# ProPrj_Custom_Keyboard_2025-10-10.net
KiCad netlist of a schematic drawn in EasyEDA Pro
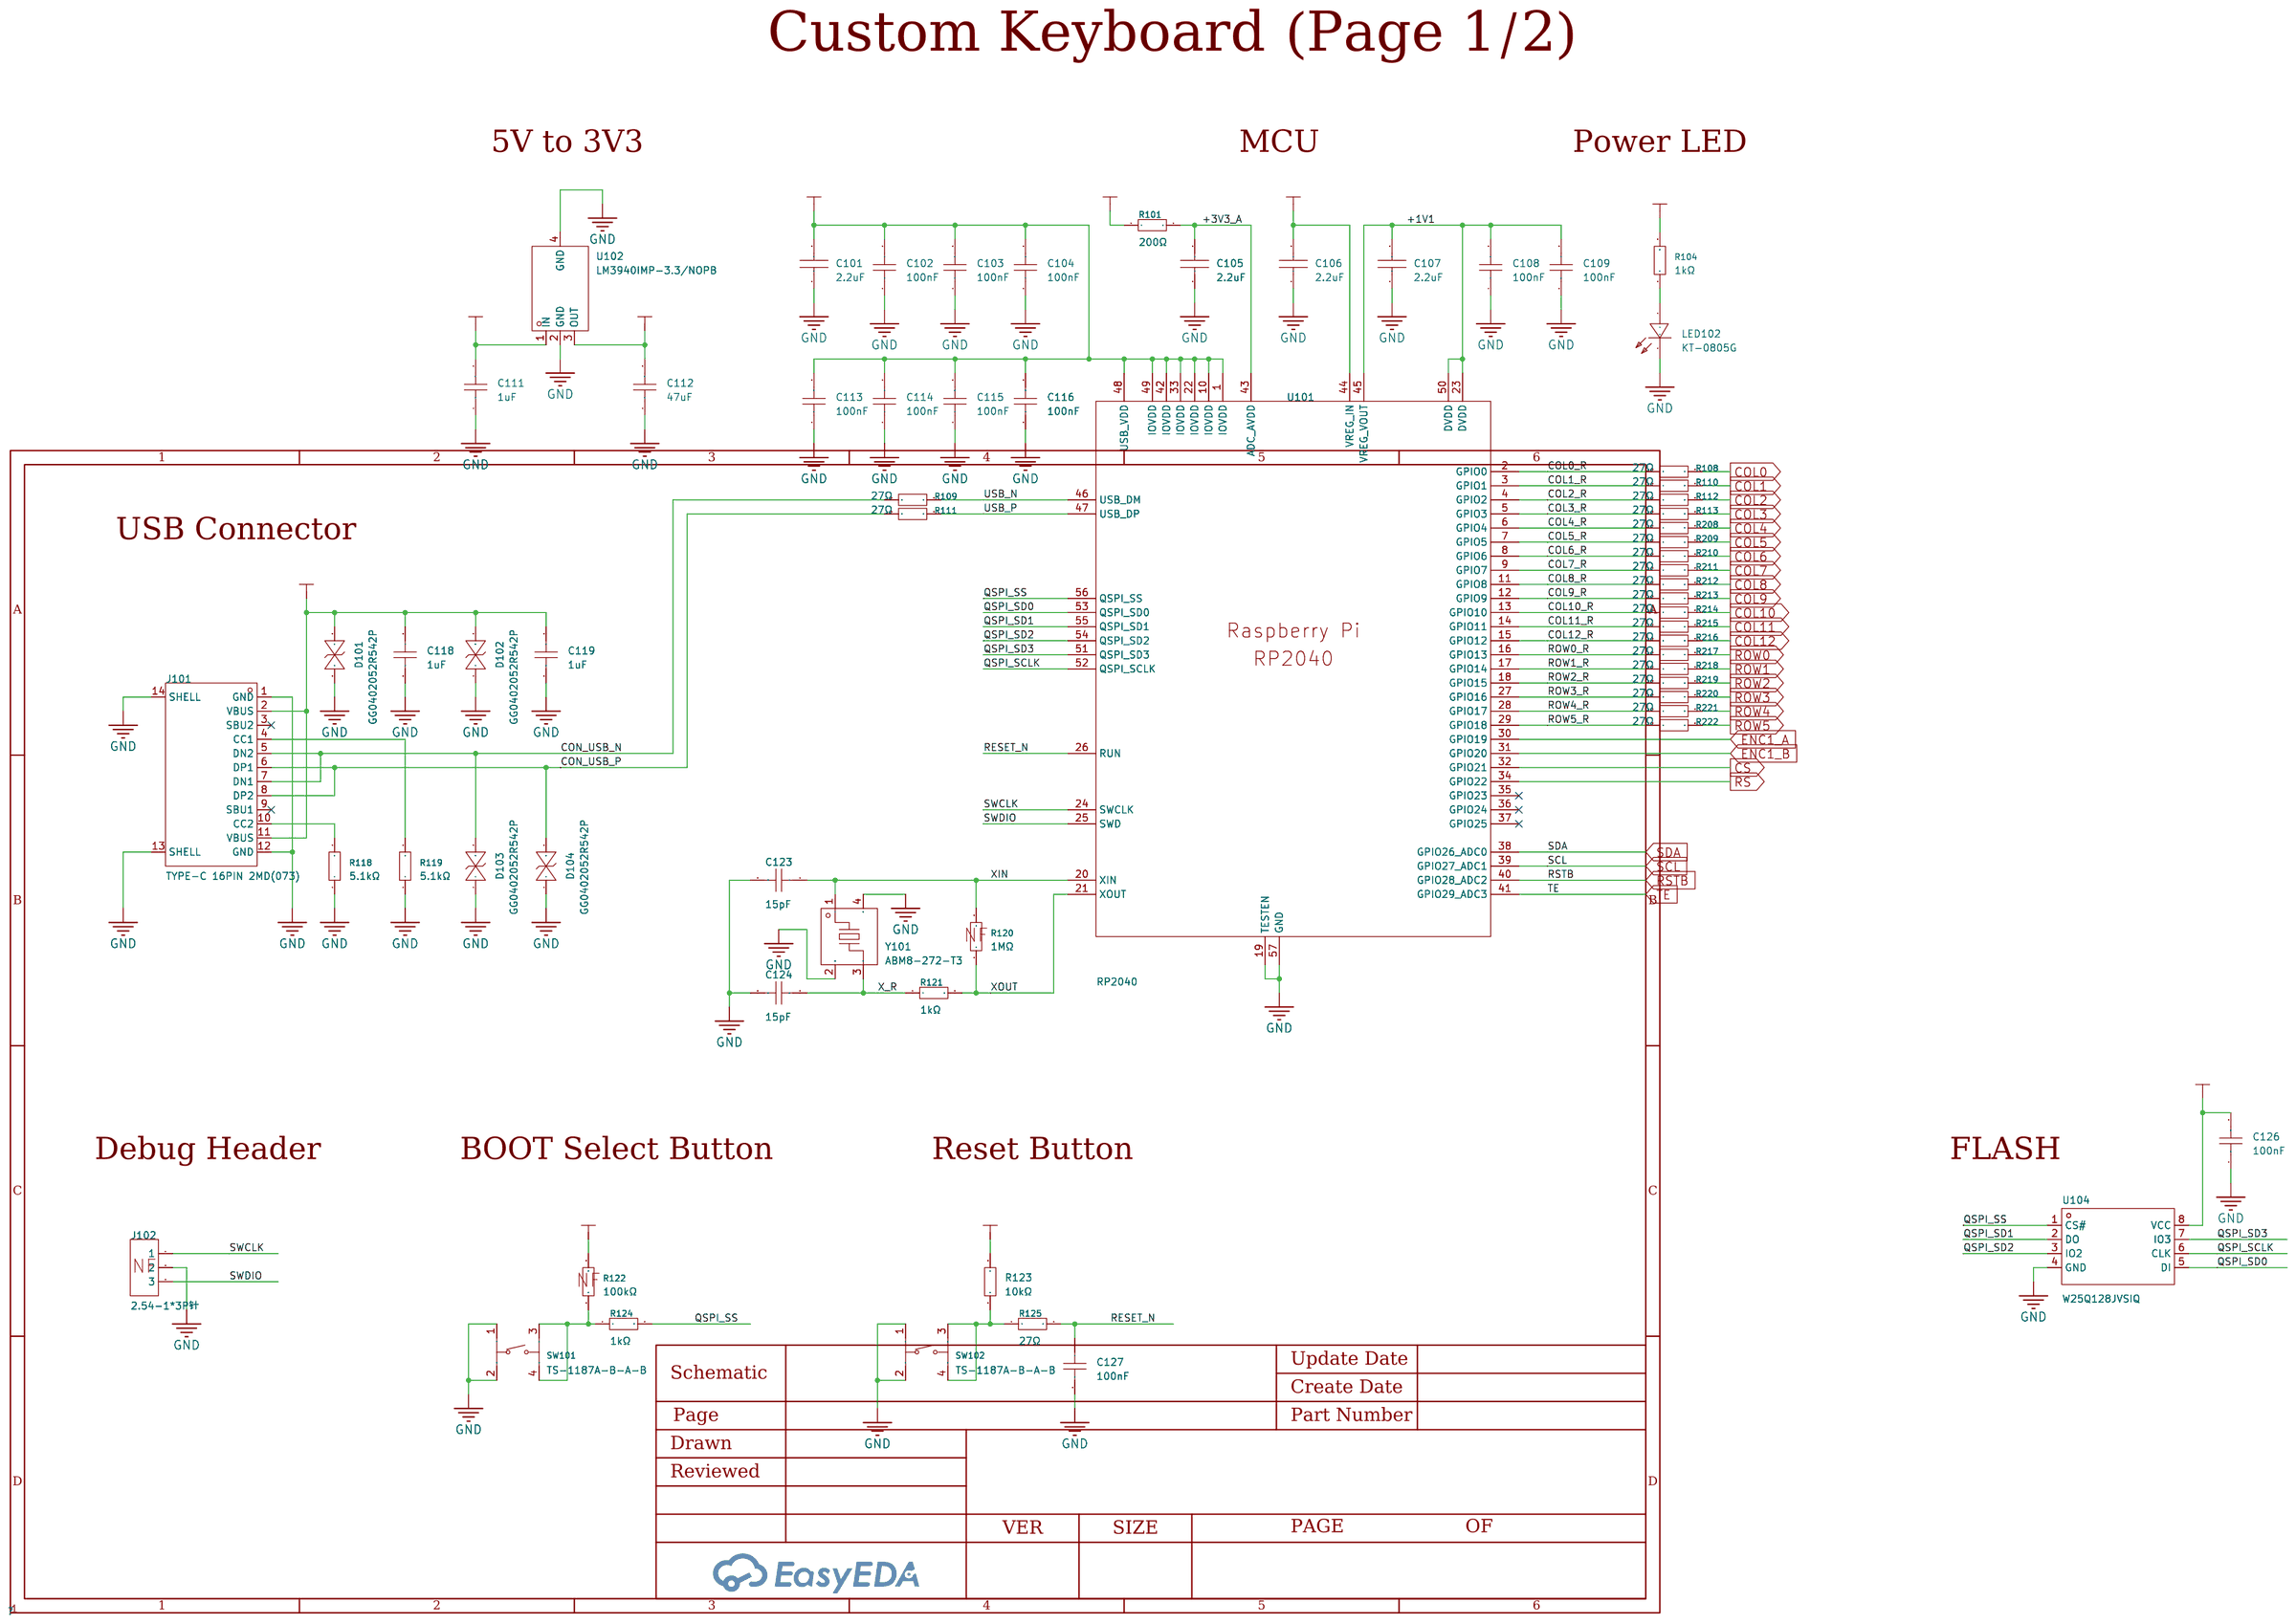
[diagram p0: MCU]
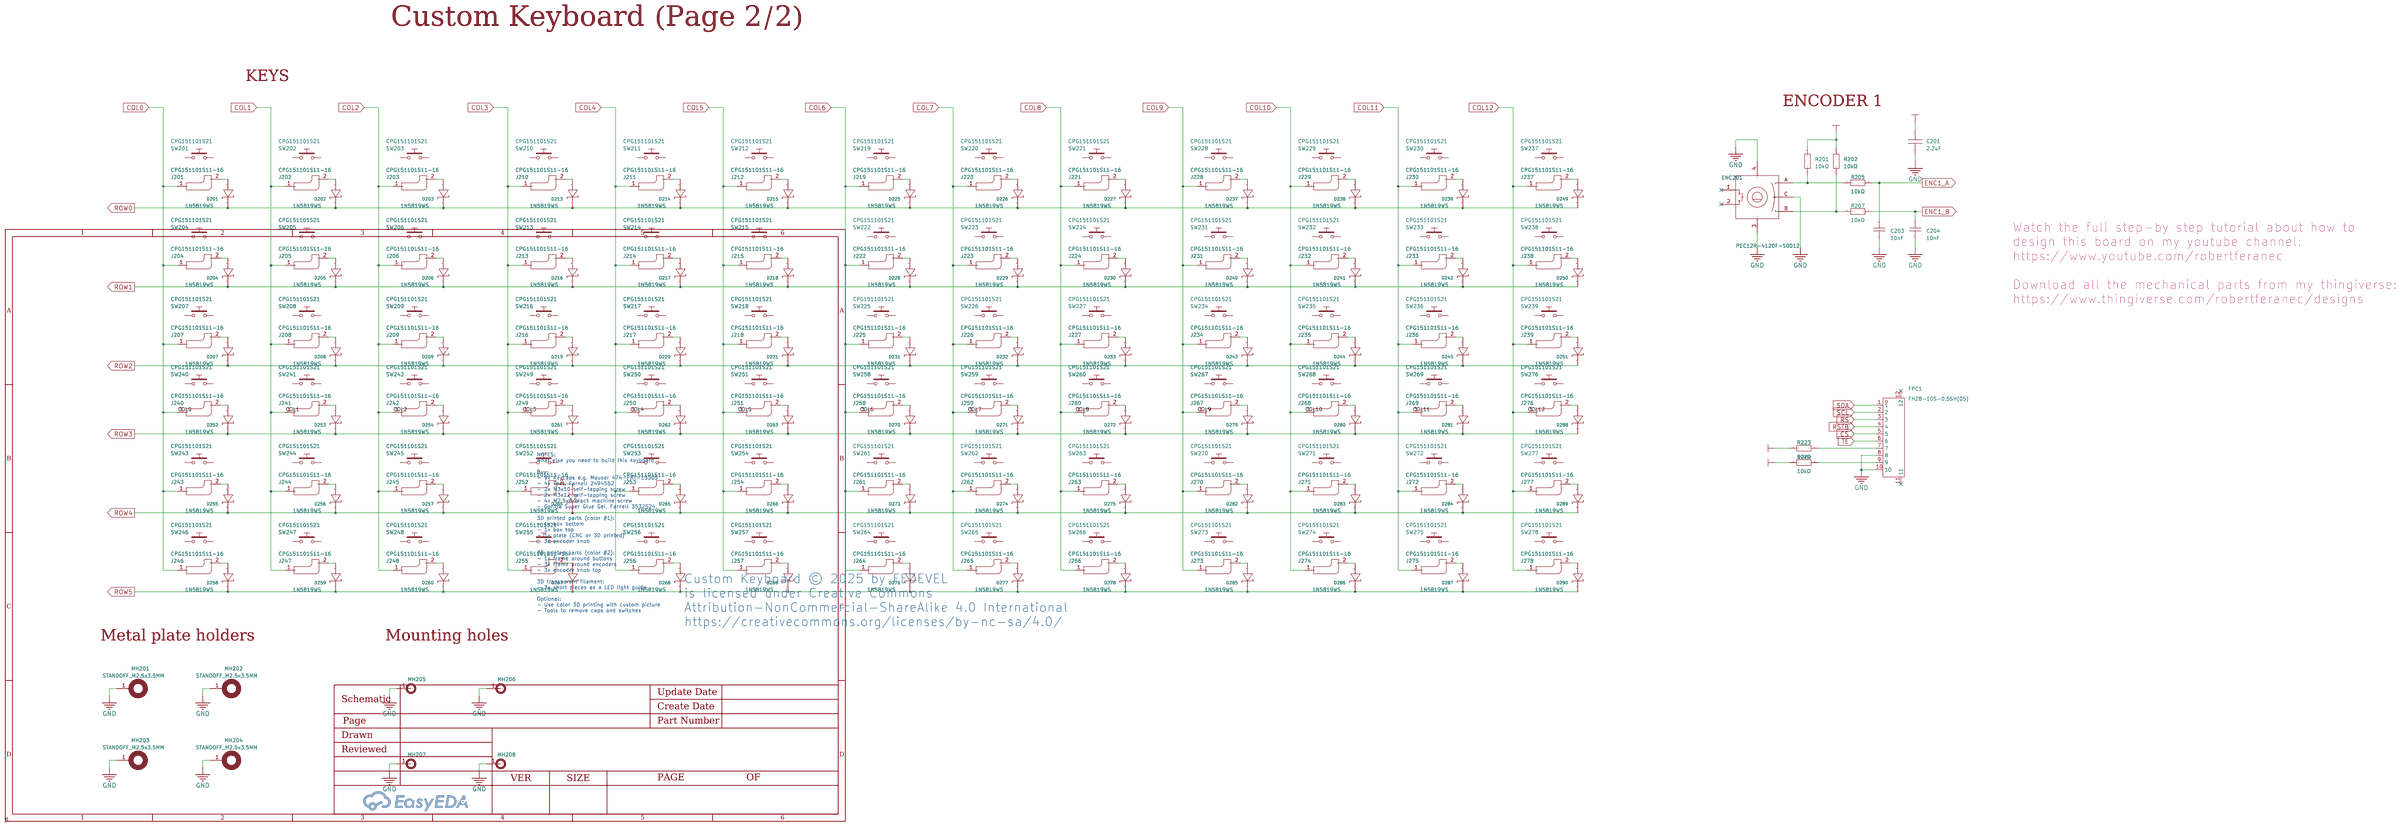
[diagram p1: OTHER]

(export (version "E")
  (design (tool "Eeschema 10.0.6"))
  (components
    (comp (ref "C101")
      (value "2.2uF")
      (footprint "easyedapro:C0402")
      (fields
        (field (name "Manufacturer Part") "CL05A225MQ5NSNC")
        (field (name "Manufacturer") "SAMSUNG(三星)")
      )
      (libsource (lib "easyedapro") (part "CL05A225MQ5NSNC"))
    )
    (comp (ref "C102")
      (value "100nF")
      (footprint "easyedapro:C0402")
      (fields
        (field (name "Manufacturer Part") "CL05B104KO5NNNC")
        (field (name "Manufacturer") "SAMSUNG(三星)")
      )
      (libsource (lib "easyedapro") (part "CL05B104KO5NNNC"))
    )
    (comp (ref "C103")
      (value "100nF")
      (footprint "easyedapro:C0402")
      (fields
        (field (name "Manufacturer Part") "CL05B104KO5NNNC")
        (field (name "Manufacturer") "SAMSUNG(三星)")
      )
      (libsource (lib "easyedapro") (part "CL05B104KO5NNNC"))
    )
    (comp (ref "C104")
      (value "100nF")
      (footprint "easyedapro:C0402")
      (fields
        (field (name "Manufacturer Part") "CL05B104KO5NNNC")
        (field (name "Manufacturer") "SAMSUNG(三星)")
      )
      (libsource (lib "easyedapro") (part "CL05B104KO5NNNC"))
    )
    (comp (ref "C105")
      (value "2.2uF")
      (footprint "easyedapro:C0402")
      (fields
        (field (name "Manufacturer Part") "CL05A225MQ5NSNC")
        (field (name "Manufacturer") "SAMSUNG(三星)")
      )
      (libsource (lib "easyedapro") (part "CL05A225MQ5NSNC"))
    )
    (comp (ref "C106")
      (value "2.2uF")
      (footprint "easyedapro:C0402")
      (fields
        (field (name "Manufacturer Part") "CL05A225MQ5NSNC")
        (field (name "Manufacturer") "SAMSUNG(三星)")
      )
      (libsource (lib "easyedapro") (part "CL05A225MQ5NSNC"))
    )
    (comp (ref "C107")
      (value "2.2uF")
      (footprint "easyedapro:C0402")
      (fields
        (field (name "Manufacturer Part") "CL05A225MQ5NSNC")
        (field (name "Manufacturer") "SAMSUNG(三星)")
      )
      (libsource (lib "easyedapro") (part "CL05A225MQ5NSNC"))
    )
    (comp (ref "C108")
      (value "100nF")
      (footprint "easyedapro:C0402")
      (fields
        (field (name "Manufacturer Part") "CL05B104KO5NNNC")
        (field (name "Manufacturer") "SAMSUNG(三星)")
      )
      (libsource (lib "easyedapro") (part "CL05B104KO5NNNC"))
    )
    (comp (ref "C109")
      (value "100nF")
      (footprint "easyedapro:C0402")
      (fields
        (field (name "Manufacturer Part") "CL05B104KO5NNNC")
        (field (name "Manufacturer") "SAMSUNG(三星)")
      )
      (libsource (lib "easyedapro") (part "CL05B104KO5NNNC"))
    )
    (comp (ref "C111")
      (value "1uF")
      (footprint "easyedapro:C0402")
      (fields
        (field (name "Manufacturer Part") "CL05A105KA5NQNC")
        (field (name "Manufacturer") "SAMSUNG(三星)")
      )
      (libsource (lib "easyedapro") (part "CL05A105KA5NQNC"))
    )
    (comp (ref "C112")
      (value "47uF")
      (footprint "easyedapro:C1206")
      (fields
        (field (name "Manufacturer Part") "CL31A476MPHNNNE")
        (field (name "Manufacturer") "SAMSUNG(三星)")
      )
      (libsource (lib "easyedapro") (part "CL31A476MPHNNNE"))
    )
    (comp (ref "C113")
      (value "100nF")
      (footprint "easyedapro:C0402")
      (fields
        (field (name "Manufacturer Part") "CL05B104KO5NNNC")
        (field (name "Manufacturer") "SAMSUNG(三星)")
      )
      (libsource (lib "easyedapro") (part "CL05B104KO5NNNC"))
    )
    (comp (ref "C114")
      (value "100nF")
      (footprint "easyedapro:C0402")
      (fields
        (field (name "Manufacturer Part") "CL05B104KO5NNNC")
        (field (name "Manufacturer") "SAMSUNG(三星)")
      )
      (libsource (lib "easyedapro") (part "CL05B104KO5NNNC"))
    )
    (comp (ref "C115")
      (value "100nF")
      (footprint "easyedapro:C0402")
      (fields
        (field (name "Manufacturer Part") "CL05B104KO5NNNC")
        (field (name "Manufacturer") "SAMSUNG(三星)")
      )
      (libsource (lib "easyedapro") (part "CL05B104KO5NNNC"))
    )
    (comp (ref "C116")
      (value "100nF")
      (footprint "easyedapro:C0402")
      (fields
        (field (name "Manufacturer Part") "CL05B104KO5NNNC")
        (field (name "Manufacturer") "SAMSUNG(三星)")
      )
      (libsource (lib "easyedapro") (part "CL05B104KO5NNNC"))
    )
    (comp (ref "C118")
      (value "1uF")
      (footprint "easyedapro:C0402")
      (fields
        (field (name "Manufacturer Part") "CL05A105KA5NQNC")
        (field (name "Manufacturer") "SAMSUNG(三星)")
      )
      (libsource (lib "easyedapro") (part "CL05A105KA5NQNC"))
    )
    (comp (ref "C119")
      (value "1uF")
      (footprint "easyedapro:C0402")
      (fields
        (field (name "Manufacturer Part") "CL05A105KA5NQNC")
        (field (name "Manufacturer") "SAMSUNG(三星)")
      )
      (libsource (lib "easyedapro") (part "CL05A105KA5NQNC"))
    )
    (comp (ref "C123")
      (value "15pF")
      (footprint "easyedapro:C0402")
      (fields
        (field (name "Manufacturer Part") "CL05C150JB5NNNC")
        (field (name "Manufacturer") "SAMSUNG(三星)")
      )
      (libsource (lib "easyedapro") (part "CL05C150JB5NNNC"))
    )
    (comp (ref "C124")
      (value "15pF")
      (footprint "easyedapro:C0402")
      (fields
        (field (name "Manufacturer Part") "CL05C150JB5NNNC")
        (field (name "Manufacturer") "SAMSUNG(三星)")
      )
      (libsource (lib "easyedapro") (part "CL05C150JB5NNNC"))
    )
    (comp (ref "C126")
      (value "100nF")
      (footprint "easyedapro:C0402")
      (fields
        (field (name "Manufacturer Part") "CL05B104KO5NNNC")
        (field (name "Manufacturer") "SAMSUNG(三星)")
      )
      (libsource (lib "easyedapro") (part "CL05B104KO5NNNC"))
    )
    (comp (ref "C127")
      (value "100nF")
      (footprint "easyedapro:C0402")
      (fields
        (field (name "Manufacturer Part") "CL05B104KO5NNNC")
        (field (name "Manufacturer") "SAMSUNG(三星)")
      )
      (libsource (lib "easyedapro") (part "CL05B104KO5NNNC"))
    )
    (comp (ref "D101")
      (value "GG0402052R542P")
      (footprint "easyedapro:D0402-BI")
      (fields (field (name "Manufacturer") "Kyocera AVX"))
      (libsource (lib "easyedapro") (part "GG0402052R542P"))
    )
    (comp (ref "D102")
      (value "GG0402052R542P")
      (footprint "easyedapro:D0402-BI")
      (fields (field (name "Manufacturer") "Kyocera AVX"))
      (libsource (lib "easyedapro") (part "GG0402052R542P"))
    )
    (comp (ref "D103")
      (value "GG0402052R542P")
      (footprint "easyedapro:D0402-BI")
      (fields (field (name "Manufacturer") "Kyocera AVX"))
      (libsource (lib "easyedapro") (part "GG0402052R542P"))
    )
    (comp (ref "D104")
      (value "GG0402052R542P")
      (footprint "easyedapro:D0402-BI")
      (fields (field (name "Manufacturer") "Kyocera AVX"))
      (libsource (lib "easyedapro") (part "GG0402052R542P"))
    )
    (comp (ref "J101")
      (value "TYPE-C 16PIN 2MD(073)")
      (footprint "easyedapro:USB-C-SMD_TYPE-C-6PIN-2MD-073")
      (fields (field (name "Manufacturer") "SHOU HAN(首韩)"))
      (libsource (lib "easyedapro") (part "TYPE-C 16PIN 2MD(073)"))
    )
    (comp (ref "J102")
      (value "2.54-1*3P针")
      (footprint "easyedapro:HDR-TH_3P-P2.54-V-M-1")
      (fields (field (name "Manufacturer") "BOOMELE(博穆精密)"))
      (libsource (lib "easyedapro") (part "Header-Male-2.54_1x3"))
    )
    (comp (ref "LED102")
      (value "KT-0805G")
      (footprint "easyedapro:LED0805-R-RD")
      (fields (field (name "Manufacturer") "KENTO"))
      (libsource (lib "easyedapro") (part "0805G (Green)"))
    )
    (comp (ref "R101")
      (value "200Ω")
      (footprint "easyedapro:R0402")
      (fields
        (field (name "Manufacturer Part") "0402WGF2000TCE")
        (field (name "Manufacturer") "UNI-ROYAL(厚声)")
      )
      (libsource (lib "easyedapro") (part "0402WGF2000TCE"))
    )
    (comp (ref "R104")
      (value "1kΩ")
      (footprint "easyedapro:R0402")
      (fields
        (field (name "Manufacturer Part") "0402WGF1001TCE")
        (field (name "Manufacturer") "UNI-ROYAL(厚声)")
      )
      (libsource (lib "easyedapro") (part "0402WGF1001TCE"))
    )
    (comp (ref "R108")
      (value "27Ω")
      (footprint "easyedapro:R0402")
      (fields
        (field (name "Manufacturer Part") "0402WGF270JTCE")
        (field (name "Manufacturer") "UNI-ROYAL(厚声)")
      )
      (libsource (lib "easyedapro") (part "0402WGF270JTCE"))
    )
    (comp (ref "R109")
      (value "27Ω")
      (footprint "easyedapro:R0402")
      (fields
        (field (name "Manufacturer Part") "0402WGF270JTCE")
        (field (name "Manufacturer") "UNI-ROYAL(厚声)")
      )
      (libsource (lib "easyedapro") (part "0402WGF270JTCE"))
    )
    (comp (ref "R110")
      (value "27Ω")
      (footprint "easyedapro:R0402")
      (fields
        (field (name "Manufacturer Part") "0402WGF270JTCE")
        (field (name "Manufacturer") "UNI-ROYAL(厚声)")
      )
      (libsource (lib "easyedapro") (part "0402WGF270JTCE"))
    )
    (comp (ref "R111")
      (value "27Ω")
      (footprint "easyedapro:R0402")
      (fields
        (field (name "Manufacturer Part") "0402WGF270JTCE")
        (field (name "Manufacturer") "UNI-ROYAL(厚声)")
      )
      (libsource (lib "easyedapro") (part "0402WGF270JTCE"))
    )
    (comp (ref "R112")
      (value "27Ω")
      (footprint "easyedapro:R0402")
      (fields
        (field (name "Manufacturer Part") "0402WGF270JTCE")
        (field (name "Manufacturer") "UNI-ROYAL(厚声)")
      )
      (libsource (lib "easyedapro") (part "0402WGF270JTCE"))
    )
    (comp (ref "R113")
      (value "27Ω")
      (footprint "easyedapro:R0402")
      (fields
        (field (name "Manufacturer Part") "0402WGF270JTCE")
        (field (name "Manufacturer") "UNI-ROYAL(厚声)")
      )
      (libsource (lib "easyedapro") (part "0402WGF270JTCE"))
    )
    (comp (ref "R118")
      (value "5.1kΩ")
      (footprint "easyedapro:R0402")
      (fields
        (field (name "Manufacturer Part") "0402WGF5101TCE")
        (field (name "Manufacturer") "UNI-ROYAL(厚声)")
      )
      (libsource (lib "easyedapro") (part "0402WGF5101TCE"))
    )
    (comp (ref "R119")
      (value "5.1kΩ")
      (footprint "easyedapro:R0402")
      (fields
        (field (name "Manufacturer Part") "0402WGF5101TCE")
        (field (name "Manufacturer") "UNI-ROYAL(厚声)")
      )
      (libsource (lib "easyedapro") (part "0402WGF5101TCE"))
    )
    (comp (ref "R120")
      (value "1MΩ")
      (footprint "easyedapro:R0402")
      (fields
        (field (name "Manufacturer Part") "0402WGF1004TCE")
        (field (name "Manufacturer") "UNI-ROYAL(厚声)")
      )
      (libsource (lib "easyedapro") (part "0402WGF1004TCE"))
    )
    (comp (ref "R121")
      (value "1kΩ")
      (footprint "easyedapro:R0402")
      (fields
        (field (name "Manufacturer Part") "0402WGF1001TCE")
        (field (name "Manufacturer") "UNI-ROYAL(厚声)")
      )
      (libsource (lib "easyedapro") (part "0402WGF1001TCE"))
    )
    (comp (ref "R122")
      (value "100kΩ")
      (footprint "easyedapro:R0402")
      (fields
        (field (name "Manufacturer Part") "0402WGF1003TCE")
        (field (name "Manufacturer") "UNI-ROYAL(厚声)")
      )
      (libsource (lib "easyedapro") (part "0402WGF1003TCE"))
    )
    (comp (ref "R123")
      (value "10kΩ")
      (footprint "easyedapro:R0402")
      (fields
        (field (name "Manufacturer Part") "0402WGF1002TCE")
        (field (name "Manufacturer") "UNI-ROYAL(厚声)")
      )
      (libsource (lib "easyedapro") (part "0402WGF1002TCE"))
    )
    (comp (ref "R124")
      (value "1kΩ")
      (footprint "easyedapro:R0402")
      (fields
        (field (name "Manufacturer Part") "0402WGF1001TCE")
        (field (name "Manufacturer") "UNI-ROYAL(厚声)")
      )
      (libsource (lib "easyedapro") (part "0402WGF1001TCE"))
    )
    (comp (ref "R125")
      (value "27Ω")
      (footprint "easyedapro:R0402")
      (fields
        (field (name "Manufacturer Part") "0402WGF270JTCE")
        (field (name "Manufacturer") "UNI-ROYAL(厚声)")
      )
      (libsource (lib "easyedapro") (part "0402WGF270JTCE"))
    )
    (comp (ref "R208")
      (value "27Ω")
      (footprint "easyedapro:R0402")
      (fields
        (field (name "Manufacturer Part") "0402WGF270JTCE")
        (field (name "Manufacturer") "UNI-ROYAL(厚声)")
      )
      (libsource (lib "easyedapro") (part "0402WGF270JTCE"))
    )
    (comp (ref "R209")
      (value "27Ω")
      (footprint "easyedapro:R0402")
      (fields
        (field (name "Manufacturer Part") "0402WGF270JTCE")
        (field (name "Manufacturer") "UNI-ROYAL(厚声)")
      )
      (libsource (lib "easyedapro") (part "0402WGF270JTCE"))
    )
    (comp (ref "R210")
      (value "27Ω")
      (footprint "easyedapro:R0402")
      (fields
        (field (name "Manufacturer Part") "0402WGF270JTCE")
        (field (name "Manufacturer") "UNI-ROYAL(厚声)")
      )
      (libsource (lib "easyedapro") (part "0402WGF270JTCE"))
    )
    (comp (ref "R211")
      (value "27Ω")
      (footprint "easyedapro:R0402")
      (fields
        (field (name "Manufacturer Part") "0402WGF270JTCE")
        (field (name "Manufacturer") "UNI-ROYAL(厚声)")
      )
      (libsource (lib "easyedapro") (part "0402WGF270JTCE"))
    )
    (comp (ref "R212")
      (value "27Ω")
      (footprint "easyedapro:R0402")
      (fields
        (field (name "Manufacturer Part") "0402WGF270JTCE")
        (field (name "Manufacturer") "UNI-ROYAL(厚声)")
      )
      (libsource (lib "easyedapro") (part "0402WGF270JTCE"))
    )
    (comp (ref "R213")
      (value "27Ω")
      (footprint "easyedapro:R0402")
      (fields
        (field (name "Manufacturer Part") "0402WGF270JTCE")
        (field (name "Manufacturer") "UNI-ROYAL(厚声)")
      )
      (libsource (lib "easyedapro") (part "0402WGF270JTCE"))
    )
    (comp (ref "R214")
      (value "27Ω")
      (footprint "easyedapro:R0402")
      (fields
        (field (name "Manufacturer Part") "0402WGF270JTCE")
        (field (name "Manufacturer") "UNI-ROYAL(厚声)")
      )
      (libsource (lib "easyedapro") (part "0402WGF270JTCE"))
    )
    (comp (ref "R215")
      (value "27Ω")
      (footprint "easyedapro:R0402")
      (fields
        (field (name "Manufacturer Part") "0402WGF270JTCE")
        (field (name "Manufacturer") "UNI-ROYAL(厚声)")
      )
      (libsource (lib "easyedapro") (part "0402WGF270JTCE"))
    )
    (comp (ref "R216")
      (value "27Ω")
      (footprint "easyedapro:R0402")
      (fields
        (field (name "Manufacturer Part") "0402WGF270JTCE")
        (field (name "Manufacturer") "UNI-ROYAL(厚声)")
      )
      (libsource (lib "easyedapro") (part "0402WGF270JTCE"))
    )
    (comp (ref "R217")
      (value "27Ω")
      (footprint "easyedapro:R0402")
      (fields
        (field (name "Manufacturer Part") "0402WGF270JTCE")
        (field (name "Manufacturer") "UNI-ROYAL(厚声)")
      )
      (libsource (lib "easyedapro") (part "0402WGF270JTCE"))
    )
    (comp (ref "R218")
      (value "27Ω")
      (footprint "easyedapro:R0402")
      (fields
        (field (name "Manufacturer Part") "0402WGF270JTCE")
        (field (name "Manufacturer") "UNI-ROYAL(厚声)")
      )
      (libsource (lib "easyedapro") (part "0402WGF270JTCE"))
    )
    (comp (ref "R219")
      (value "27Ω")
      (footprint "easyedapro:R0402")
      (fields
        (field (name "Manufacturer Part") "0402WGF270JTCE")
        (field (name "Manufacturer") "UNI-ROYAL(厚声)")
      )
      (libsource (lib "easyedapro") (part "0402WGF270JTCE"))
    )
    (comp (ref "R220")
      (value "27Ω")
      (footprint "easyedapro:R0402")
      (fields
        (field (name "Manufacturer Part") "0402WGF270JTCE")
        (field (name "Manufacturer") "UNI-ROYAL(厚声)")
      )
      (libsource (lib "easyedapro") (part "0402WGF270JTCE"))
    )
    (comp (ref "R221")
      (value "27Ω")
      (footprint "easyedapro:R0402")
      (fields
        (field (name "Manufacturer Part") "0402WGF270JTCE")
        (field (name "Manufacturer") "UNI-ROYAL(厚声)")
      )
      (libsource (lib "easyedapro") (part "0402WGF270JTCE"))
    )
    (comp (ref "R222")
      (value "27Ω")
      (footprint "easyedapro:R0402")
      (fields
        (field (name "Manufacturer Part") "0402WGF270JTCE")
        (field (name "Manufacturer") "UNI-ROYAL(厚声)")
      )
      (libsource (lib "easyedapro") (part "0402WGF270JTCE"))
    )
    (comp (ref "SW101")
      (value "TS-1187A-B-A-B")
      (footprint "easyedapro:SW-SMD_4P-L5.1-W5.1-P3.70-LS6.5-TL-2")
      (fields (field (name "Manufacturer") "XKB Connectivity(中国星坤)"))
      (libsource (lib "easyedapro") (part "TS-1187A-B-A-B"))
    )
    (comp (ref "SW102")
      (value "TS-1187A-B-A-B")
      (footprint "easyedapro:SW-SMD_4P-L5.1-W5.1-P3.70-LS6.5-TL-2")
      (fields (field (name "Manufacturer") "XKB Connectivity(中国星坤)"))
      (libsource (lib "easyedapro") (part "TS-1187A-B-A-B"))
    )
    (comp (ref "U101")
      (value "RP2040")
      (footprint "easyedapro:LQFN-56_L7.0-W7.0-P0.4-EP_1")
      (fields (field (name "Manufacturer") "Raspberry Pi(树莓派)"))
      (libsource (lib "easyedapro") (part "RP2040_C2040_RF_v1.0"))
    )
    (comp (ref "U102")
      (value "LM3940IMP-3.3/NOPB")
      (footprint "easyedapro:SOT-223_L6.5-W3.5-P2.30-LS7.0-BR")
      (fields (field (name "Manufacturer") "TI(德州仪器)"))
      (libsource (lib "easyedapro") (part "LM3940IMP-3.3/NOPB"))
    )
    (comp (ref "U104")
      (value "W25Q128JVSIQ")
      (footprint "easyedapro:SOIC-8_L5.3-W5.3-P1.27-LS8.0-BL")
      (fields (field (name "Manufacturer") "WINBOND(华邦)"))
      (libsource (lib "easyedapro") (part "W25Q128JVSIQTR"))
    )
    (comp (ref "Y101")
      (value "ABM8-272-T3")
      (footprint "easyedapro:CRYSTAL-SMD_4P-L3.2-W2.5-BL")
      (fields (field (name "Manufacturer") "ABRACON"))
      (libsource (lib "easyedapro") (part "ABM8-272-T3_C20625731"))
    )
    (comp (ref "C201")
      (value "2.2uF")
      (footprint "easyedapro:C0402")
      (fields
        (field (name "Manufacturer Part") "CL05A225MQ5NSNC")
        (field (name "Manufacturer") "SAMSUNG(三星)")
      )
      (libsource (lib "easyedapro") (part "CL05A225MQ5NSNC"))
    )
    (comp (ref "C203")
      (value "10nF")
      (footprint "easyedapro:C0402")
      (fields
        (field (name "Manufacturer Part") "CL05B103KB5NNNC")
        (field (name "Manufacturer") "SAMSUNG(三星)")
      )
      (libsource (lib "easyedapro") (part "CL05B103KB5NNNC"))
    )
    (comp (ref "C204")
      (value "10nF")
      (footprint "easyedapro:C0402")
      (fields
        (field (name "Manufacturer Part") "CL05B103KB5NNNC")
        (field (name "Manufacturer") "SAMSUNG(三星)")
      )
      (libsource (lib "easyedapro") (part "CL05B103KB5NNNC"))
    )
    (comp (ref "D201")
      (value "1N5819WS")
      (footprint "easyedapro:SOD-323_L1.8-W1.3-LS2.5-RD")
      (description "Forward Voltage (Vf@If):600mV@1A Reverse Voltage (Vr):40V Average Rectified Current (Io):1A")
      (fields (field (name "Manufacturer") "Hottech(合科泰)"))
      (libsource (lib "easyedapro") (part "1N5819WS"))
    )
    (comp (ref "D202")
      (value "1N5819WS")
      (footprint "easyedapro:SOD-323_L1.8-W1.3-LS2.5-RD")
      (description "Forward Voltage (Vf@If):600mV@1A Reverse Voltage (Vr):40V Average Rectified Current (Io):1A")
      (fields (field (name "Manufacturer") "Hottech(合科泰)"))
      (libsource (lib "easyedapro") (part "1N5819WS"))
    )
    (comp (ref "D203")
      (value "1N5819WS")
      (footprint "easyedapro:SOD-323_L1.8-W1.3-LS2.5-RD")
      (description "Forward Voltage (Vf@If):600mV@1A Reverse Voltage (Vr):40V Average Rectified Current (Io):1A")
      (fields (field (name "Manufacturer") "Hottech(合科泰)"))
      (libsource (lib "easyedapro") (part "1N5819WS"))
    )
    (comp (ref "D204")
      (value "1N5819WS")
      (footprint "easyedapro:SOD-323_L1.8-W1.3-LS2.5-RD")
      (description "Forward Voltage (Vf@If):600mV@1A Reverse Voltage (Vr):40V Average Rectified Current (Io):1A")
      (fields (field (name "Manufacturer") "Hottech(合科泰)"))
      (libsource (lib "easyedapro") (part "1N5819WS"))
    )
    (comp (ref "D205")
      (value "1N5819WS")
      (footprint "easyedapro:SOD-323_L1.8-W1.3-LS2.5-RD")
      (description "Forward Voltage (Vf@If):600mV@1A Reverse Voltage (Vr):40V Average Rectified Current (Io):1A")
      (fields (field (name "Manufacturer") "Hottech(合科泰)"))
      (libsource (lib "easyedapro") (part "1N5819WS"))
    )
    (comp (ref "D206")
      (value "1N5819WS")
      (footprint "easyedapro:SOD-323_L1.8-W1.3-LS2.5-RD")
      (description "Forward Voltage (Vf@If):600mV@1A Reverse Voltage (Vr):40V Average Rectified Current (Io):1A")
      (fields (field (name "Manufacturer") "Hottech(合科泰)"))
      (libsource (lib "easyedapro") (part "1N5819WS"))
    )
    (comp (ref "D207")
      (value "1N5819WS")
      (footprint "easyedapro:SOD-323_L1.8-W1.3-LS2.5-RD")
      (description "Forward Voltage (Vf@If):600mV@1A Reverse Voltage (Vr):40V Average Rectified Current (Io):1A")
      (fields (field (name "Manufacturer") "Hottech(合科泰)"))
      (libsource (lib "easyedapro") (part "1N5819WS"))
    )
    (comp (ref "D208")
      (value "1N5819WS")
      (footprint "easyedapro:SOD-323_L1.8-W1.3-LS2.5-RD")
      (description "Forward Voltage (Vf@If):600mV@1A Reverse Voltage (Vr):40V Average Rectified Current (Io):1A")
      (fields (field (name "Manufacturer") "Hottech(合科泰)"))
      (libsource (lib "easyedapro") (part "1N5819WS"))
    )
    (comp (ref "D209")
      (value "1N5819WS")
      (footprint "easyedapro:SOD-323_L1.8-W1.3-LS2.5-RD")
      (description "Forward Voltage (Vf@If):600mV@1A Reverse Voltage (Vr):40V Average Rectified Current (Io):1A")
      (fields (field (name "Manufacturer") "Hottech(合科泰)"))
      (libsource (lib "easyedapro") (part "1N5819WS"))
    )
    (comp (ref "D213")
      (value "1N5819WS")
      (footprint "easyedapro:SOD-323_L1.8-W1.3-LS2.5-RD")
      (description "Forward Voltage (Vf@If):600mV@1A Reverse Voltage (Vr):40V Average Rectified Current (Io):1A")
      (fields (field (name "Manufacturer") "Hottech(合科泰)"))
      (libsource (lib "easyedapro") (part "1N5819WS"))
    )
    (comp (ref "D214")
      (value "1N5819WS")
      (footprint "easyedapro:SOD-323_L1.8-W1.3-LS2.5-RD")
      (description "Forward Voltage (Vf@If):600mV@1A Reverse Voltage (Vr):40V Average Rectified Current (Io):1A")
      (fields (field (name "Manufacturer") "Hottech(合科泰)"))
      (libsource (lib "easyedapro") (part "1N5819WS"))
    )
    (comp (ref "D215")
      (value "1N5819WS")
      (footprint "easyedapro:SOD-323_L1.8-W1.3-LS2.5-RD")
      (description "Forward Voltage (Vf@If):600mV@1A Reverse Voltage (Vr):40V Average Rectified Current (Io):1A")
      (fields (field (name "Manufacturer") "Hottech(合科泰)"))
      (libsource (lib "easyedapro") (part "1N5819WS"))
    )
    (comp (ref "D216")
      (value "1N5819WS")
      (footprint "easyedapro:SOD-323_L1.8-W1.3-LS2.5-RD")
      (description "Forward Voltage (Vf@If):600mV@1A Reverse Voltage (Vr):40V Average Rectified Current (Io):1A")
      (fields (field (name "Manufacturer") "Hottech(合科泰)"))
      (libsource (lib "easyedapro") (part "1N5819WS"))
    )
    (comp (ref "D217")
      (value "1N5819WS")
      (footprint "easyedapro:SOD-323_L1.8-W1.3-LS2.5-RD")
      (description "Forward Voltage (Vf@If):600mV@1A Reverse Voltage (Vr):40V Average Rectified Current (Io):1A")
      (fields (field (name "Manufacturer") "Hottech(合科泰)"))
      (libsource (lib "easyedapro") (part "1N5819WS"))
    )
    (comp (ref "D218")
      (value "1N5819WS")
      (footprint "easyedapro:SOD-323_L1.8-W1.3-LS2.5-RD")
      (description "Forward Voltage (Vf@If):600mV@1A Reverse Voltage (Vr):40V Average Rectified Current (Io):1A")
      (fields (field (name "Manufacturer") "Hottech(合科泰)"))
      (libsource (lib "easyedapro") (part "1N5819WS"))
    )
    (comp (ref "D219")
      (value "1N5819WS")
      (footprint "easyedapro:SOD-323_L1.8-W1.3-LS2.5-RD")
      (description "Forward Voltage (Vf@If):600mV@1A Reverse Voltage (Vr):40V Average Rectified Current (Io):1A")
      (fields (field (name "Manufacturer") "Hottech(合科泰)"))
      (libsource (lib "easyedapro") (part "1N5819WS"))
    )
    (comp (ref "D220")
      (value "1N5819WS")
      (footprint "easyedapro:SOD-323_L1.8-W1.3-LS2.5-RD")
      (description "Forward Voltage (Vf@If):600mV@1A Reverse Voltage (Vr):40V Average Rectified Current (Io):1A")
      (fields (field (name "Manufacturer") "Hottech(合科泰)"))
      (libsource (lib "easyedapro") (part "1N5819WS"))
    )
    (comp (ref "D221")
      (value "1N5819WS")
      (footprint "easyedapro:SOD-323_L1.8-W1.3-LS2.5-RD")
      (description "Forward Voltage (Vf@If):600mV@1A Reverse Voltage (Vr):40V Average Rectified Current (Io):1A")
      (fields (field (name "Manufacturer") "Hottech(合科泰)"))
      (libsource (lib "easyedapro") (part "1N5819WS"))
    )
    (comp (ref "D225")
      (value "1N5819WS")
      (footprint "easyedapro:SOD-323_L1.8-W1.3-LS2.5-RD")
      (description "Forward Voltage (Vf@If):600mV@1A Reverse Voltage (Vr):40V Average Rectified Current (Io):1A")
      (fields (field (name "Manufacturer") "Hottech(合科泰)"))
      (libsource (lib "easyedapro") (part "1N5819WS"))
    )
    (comp (ref "D226")
      (value "1N5819WS")
      (footprint "easyedapro:SOD-323_L1.8-W1.3-LS2.5-RD")
      (description "Forward Voltage (Vf@If):600mV@1A Reverse Voltage (Vr):40V Average Rectified Current (Io):1A")
      (fields (field (name "Manufacturer") "Hottech(合科泰)"))
      (libsource (lib "easyedapro") (part "1N5819WS"))
    )
    (comp (ref "D227")
      (value "1N5819WS")
      (footprint "easyedapro:SOD-323_L1.8-W1.3-LS2.5-RD")
      (description "Forward Voltage (Vf@If):600mV@1A Reverse Voltage (Vr):40V Average Rectified Current (Io):1A")
      (fields (field (name "Manufacturer") "Hottech(合科泰)"))
      (libsource (lib "easyedapro") (part "1N5819WS"))
    )
    (comp (ref "D228")
      (value "1N5819WS")
      (footprint "easyedapro:SOD-323_L1.8-W1.3-LS2.5-RD")
      (description "Forward Voltage (Vf@If):600mV@1A Reverse Voltage (Vr):40V Average Rectified Current (Io):1A")
      (fields (field (name "Manufacturer") "Hottech(合科泰)"))
      (libsource (lib "easyedapro") (part "1N5819WS"))
    )
    (comp (ref "D229")
      (value "1N5819WS")
      (footprint "easyedapro:SOD-323_L1.8-W1.3-LS2.5-RD")
      (description "Forward Voltage (Vf@If):600mV@1A Reverse Voltage (Vr):40V Average Rectified Current (Io):1A")
      (fields (field (name "Manufacturer") "Hottech(合科泰)"))
      (libsource (lib "easyedapro") (part "1N5819WS"))
    )
    (comp (ref "D230")
      (value "1N5819WS")
      (footprint "easyedapro:SOD-323_L1.8-W1.3-LS2.5-RD")
      (description "Forward Voltage (Vf@If):600mV@1A Reverse Voltage (Vr):40V Average Rectified Current (Io):1A")
      (fields (field (name "Manufacturer") "Hottech(合科泰)"))
      (libsource (lib "easyedapro") (part "1N5819WS"))
    )
    (comp (ref "D231")
      (value "1N5819WS")
      (footprint "easyedapro:SOD-323_L1.8-W1.3-LS2.5-RD")
      (description "Forward Voltage (Vf@If):600mV@1A Reverse Voltage (Vr):40V Average Rectified Current (Io):1A")
      (fields (field (name "Manufacturer") "Hottech(合科泰)"))
      (libsource (lib "easyedapro") (part "1N5819WS"))
    )
    (comp (ref "D232")
      (value "1N5819WS")
      (footprint "easyedapro:SOD-323_L1.8-W1.3-LS2.5-RD")
      (description "Forward Voltage (Vf@If):600mV@1A Reverse Voltage (Vr):40V Average Rectified Current (Io):1A")
      (fields (field (name "Manufacturer") "Hottech(合科泰)"))
      (libsource (lib "easyedapro") (part "1N5819WS"))
    )
    (comp (ref "D233")
      (value "1N5819WS")
      (footprint "easyedapro:SOD-323_L1.8-W1.3-LS2.5-RD")
      (description "Forward Voltage (Vf@If):600mV@1A Reverse Voltage (Vr):40V Average Rectified Current (Io):1A")
      (fields (field (name "Manufacturer") "Hottech(合科泰)"))
      (libsource (lib "easyedapro") (part "1N5819WS"))
    )
    (comp (ref "D237")
      (value "1N5819WS")
      (footprint "easyedapro:SOD-323_L1.8-W1.3-LS2.5-RD")
      (description "Forward Voltage (Vf@If):600mV@1A Reverse Voltage (Vr):40V Average Rectified Current (Io):1A")
      (fields (field (name "Manufacturer") "Hottech(合科泰)"))
      (libsource (lib "easyedapro") (part "1N5819WS"))
    )
    (comp (ref "D238")
      (value "1N5819WS")
      (footprint "easyedapro:SOD-323_L1.8-W1.3-LS2.5-RD")
      (description "Forward Voltage (Vf@If):600mV@1A Reverse Voltage (Vr):40V Average Rectified Current (Io):1A")
      (fields (field (name "Manufacturer") "Hottech(合科泰)"))
      (libsource (lib "easyedapro") (part "1N5819WS"))
    )
    (comp (ref "D239")
      (value "1N5819WS")
      (footprint "easyedapro:SOD-323_L1.8-W1.3-LS2.5-RD")
      (description "Forward Voltage (Vf@If):600mV@1A Reverse Voltage (Vr):40V Average Rectified Current (Io):1A")
      (fields (field (name "Manufacturer") "Hottech(合科泰)"))
      (libsource (lib "easyedapro") (part "1N5819WS"))
    )
    (comp (ref "D240")
      (value "1N5819WS")
      (footprint "easyedapro:SOD-323_L1.8-W1.3-LS2.5-RD")
      (description "Forward Voltage (Vf@If):600mV@1A Reverse Voltage (Vr):40V Average Rectified Current (Io):1A")
      (fields (field (name "Manufacturer") "Hottech(合科泰)"))
      (libsource (lib "easyedapro") (part "1N5819WS"))
    )
    (comp (ref "D241")
      (value "1N5819WS")
      (footprint "easyedapro:SOD-323_L1.8-W1.3-LS2.5-RD")
      (description "Forward Voltage (Vf@If):600mV@1A Reverse Voltage (Vr):40V Average Rectified Current (Io):1A")
      (fields (field (name "Manufacturer") "Hottech(合科泰)"))
      (libsource (lib "easyedapro") (part "1N5819WS"))
    )
    (comp (ref "D242")
      (value "1N5819WS")
      (footprint "easyedapro:SOD-323_L1.8-W1.3-LS2.5-RD")
      (description "Forward Voltage (Vf@If):600mV@1A Reverse Voltage (Vr):40V Average Rectified Current (Io):1A")
      (fields (field (name "Manufacturer") "Hottech(合科泰)"))
      (libsource (lib "easyedapro") (part "1N5819WS"))
    )
    (comp (ref "D243")
      (value "1N5819WS")
      (footprint "easyedapro:SOD-323_L1.8-W1.3-LS2.5-RD")
      (description "Forward Voltage (Vf@If):600mV@1A Reverse Voltage (Vr):40V Average Rectified Current (Io):1A")
      (fields (field (name "Manufacturer") "Hottech(合科泰)"))
      (libsource (lib "easyedapro") (part "1N5819WS"))
    )
    (comp (ref "D244")
      (value "1N5819WS")
      (footprint "easyedapro:SOD-323_L1.8-W1.3-LS2.5-RD")
      (description "Forward Voltage (Vf@If):600mV@1A Reverse Voltage (Vr):40V Average Rectified Current (Io):1A")
      (fields (field (name "Manufacturer") "Hottech(合科泰)"))
      (libsource (lib "easyedapro") (part "1N5819WS"))
    )
    (comp (ref "D245")
      (value "1N5819WS")
      (footprint "easyedapro:SOD-323_L1.8-W1.3-LS2.5-RD")
      (description "Forward Voltage (Vf@If):600mV@1A Reverse Voltage (Vr):40V Average Rectified Current (Io):1A")
      (fields (field (name "Manufacturer") "Hottech(合科泰)"))
      (libsource (lib "easyedapro") (part "1N5819WS"))
    )
    (comp (ref "D249")
      (value "1N5819WS")
      (footprint "easyedapro:SOD-323_L1.8-W1.3-LS2.5-RD")
      (description "Forward Voltage (Vf@If):600mV@1A Reverse Voltage (Vr):40V Average Rectified Current (Io):1A")
      (fields (field (name "Manufacturer") "Hottech(合科泰)"))
      (libsource (lib "easyedapro") (part "1N5819WS"))
    )
    (comp (ref "D250")
      (value "1N5819WS")
      (footprint "easyedapro:SOD-323_L1.8-W1.3-LS2.5-RD")
      (description "Forward Voltage (Vf@If):600mV@1A Reverse Voltage (Vr):40V Average Rectified Current (Io):1A")
      (fields (field (name "Manufacturer") "Hottech(合科泰)"))
      (libsource (lib "easyedapro") (part "1N5819WS"))
    )
    (comp (ref "D251")
      (value "1N5819WS")
      (footprint "easyedapro:SOD-323_L1.8-W1.3-LS2.5-RD")
      (description "Forward Voltage (Vf@If):600mV@1A Reverse Voltage (Vr):40V Average Rectified Current (Io):1A")
      (fields (field (name "Manufacturer") "Hottech(合科泰)"))
      (libsource (lib "easyedapro") (part "1N5819WS"))
    )
    (comp (ref "D252")
      (value "1N5819WS")
      (footprint "easyedapro:SOD-323_L1.8-W1.3-LS2.5-RD")
      (description "Forward Voltage (Vf@If):600mV@1A Reverse Voltage (Vr):40V Average Rectified Current (Io):1A")
      (fields (field (name "Manufacturer") "Hottech(合科泰)"))
      (libsource (lib "easyedapro") (part "1N5819WS"))
    )
    (comp (ref "D253")
      (value "1N5819WS")
      (footprint "easyedapro:SOD-323_L1.8-W1.3-LS2.5-RD")
      (description "Forward Voltage (Vf@If):600mV@1A Reverse Voltage (Vr):40V Average Rectified Current (Io):1A")
      (fields (field (name "Manufacturer") "Hottech(合科泰)"))
      (libsource (lib "easyedapro") (part "1N5819WS"))
    )
    (comp (ref "D254")
      (value "1N5819WS")
      (footprint "easyedapro:SOD-323_L1.8-W1.3-LS2.5-RD")
      (description "Forward Voltage (Vf@If):600mV@1A Reverse Voltage (Vr):40V Average Rectified Current (Io):1A")
      (fields (field (name "Manufacturer") "Hottech(合科泰)"))
      (libsource (lib "easyedapro") (part "1N5819WS"))
    )
    (comp (ref "D255")
      (value "1N5819WS")
      (footprint "easyedapro:SOD-323_L1.8-W1.3-LS2.5-RD")
      (description "Forward Voltage (Vf@If):600mV@1A Reverse Voltage (Vr):40V Average Rectified Current (Io):1A")
      (fields (field (name "Manufacturer") "Hottech(合科泰)"))
      (libsource (lib "easyedapro") (part "1N5819WS"))
    )
    (comp (ref "D256")
      (value "1N5819WS")
      (footprint "easyedapro:SOD-323_L1.8-W1.3-LS2.5-RD")
      (description "Forward Voltage (Vf@If):600mV@1A Reverse Voltage (Vr):40V Average Rectified Current (Io):1A")
      (fields (field (name "Manufacturer") "Hottech(合科泰)"))
      (libsource (lib "easyedapro") (part "1N5819WS"))
    )
    (comp (ref "D257")
      (value "1N5819WS")
      (footprint "easyedapro:SOD-323_L1.8-W1.3-LS2.5-RD")
      (description "Forward Voltage (Vf@If):600mV@1A Reverse Voltage (Vr):40V Average Rectified Current (Io):1A")
      (fields (field (name "Manufacturer") "Hottech(合科泰)"))
      (libsource (lib "easyedapro") (part "1N5819WS"))
    )
    (comp (ref "D258")
      (value "1N5819WS")
      (footprint "easyedapro:SOD-323_L1.8-W1.3-LS2.5-RD")
      (description "Forward Voltage (Vf@If):600mV@1A Reverse Voltage (Vr):40V Average Rectified Current (Io):1A")
      (fields (field (name "Manufacturer") "Hottech(合科泰)"))
      (libsource (lib "easyedapro") (part "1N5819WS"))
    )
    (comp (ref "D259")
      (value "1N5819WS")
      (footprint "easyedapro:SOD-323_L1.8-W1.3-LS2.5-RD")
      (description "Forward Voltage (Vf@If):600mV@1A Reverse Voltage (Vr):40V Average Rectified Current (Io):1A")
      (fields (field (name "Manufacturer") "Hottech(合科泰)"))
      (libsource (lib "easyedapro") (part "1N5819WS"))
    )
    (comp (ref "D260")
      (value "1N5819WS")
      (footprint "easyedapro:SOD-323_L1.8-W1.3-LS2.5-RD")
      (description "Forward Voltage (Vf@If):600mV@1A Reverse Voltage (Vr):40V Average Rectified Current (Io):1A")
      (fields (field (name "Manufacturer") "Hottech(合科泰)"))
      (libsource (lib "easyedapro") (part "1N5819WS"))
    )
    (comp (ref "D261")
      (value "1N5819WS")
      (footprint "easyedapro:SOD-323_L1.8-W1.3-LS2.5-RD")
      (description "Forward Voltage (Vf@If):600mV@1A Reverse Voltage (Vr):40V Average Rectified Current (Io):1A")
      (fields (field (name "Manufacturer") "Hottech(合科泰)"))
      (libsource (lib "easyedapro") (part "1N5819WS"))
    )
    (comp (ref "D262")
      (value "1N5819WS")
      (footprint "easyedapro:SOD-323_L1.8-W1.3-LS2.5-RD")
      (description "Forward Voltage (Vf@If):600mV@1A Reverse Voltage (Vr):40V Average Rectified Current (Io):1A")
      (fields (field (name "Manufacturer") "Hottech(合科泰)"))
      (libsource (lib "easyedapro") (part "1N5819WS"))
    )
    (comp (ref "D263")
      (value "1N5819WS")
      (footprint "easyedapro:SOD-323_L1.8-W1.3-LS2.5-RD")
      (description "Forward Voltage (Vf@If):600mV@1A Reverse Voltage (Vr):40V Average Rectified Current (Io):1A")
      (fields (field (name "Manufacturer") "Hottech(合科泰)"))
      (libsource (lib "easyedapro") (part "1N5819WS"))
    )
    (comp (ref "D264")
      (value "1N5819WS")
      (footprint "easyedapro:SOD-323_L1.8-W1.3-LS2.5-RD")
      (description "Forward Voltage (Vf@If):600mV@1A Reverse Voltage (Vr):40V Average Rectified Current (Io):1A")
      (fields (field (name "Manufacturer") "Hottech(合科泰)"))
      (libsource (lib "easyedapro") (part "1N5819WS"))
    )
    (comp (ref "D265")
      (value "1N5819WS")
      (footprint "easyedapro:SOD-323_L1.8-W1.3-LS2.5-RD")
      (description "Forward Voltage (Vf@If):600mV@1A Reverse Voltage (Vr):40V Average Rectified Current (Io):1A")
      (fields (field (name "Manufacturer") "Hottech(合科泰)"))
      (libsource (lib "easyedapro") (part "1N5819WS"))
    )
    (comp (ref "D266")
      (value "1N5819WS")
      (footprint "easyedapro:SOD-323_L1.8-W1.3-LS2.5-RD")
      (description "Forward Voltage (Vf@If):600mV@1A Reverse Voltage (Vr):40V Average Rectified Current (Io):1A")
      (fields (field (name "Manufacturer") "Hottech(合科泰)"))
      (libsource (lib "easyedapro") (part "1N5819WS"))
    )
    (comp (ref "D267")
      (value "1N5819WS")
      (footprint "easyedapro:SOD-323_L1.8-W1.3-LS2.5-RD")
      (description "Forward Voltage (Vf@If):600mV@1A Reverse Voltage (Vr):40V Average Rectified Current (Io):1A")
      (fields (field (name "Manufacturer") "Hottech(合科泰)"))
      (libsource (lib "easyedapro") (part "1N5819WS"))
    )
    (comp (ref "D268")
      (value "1N5819WS")
      (footprint "easyedapro:SOD-323_L1.8-W1.3-LS2.5-RD")
      (description "Forward Voltage (Vf@If):600mV@1A Reverse Voltage (Vr):40V Average Rectified Current (Io):1A")
      (fields (field (name "Manufacturer") "Hottech(合科泰)"))
      (libsource (lib "easyedapro") (part "1N5819WS"))
    )
    (comp (ref "D269")
      (value "1N5819WS")
      (footprint "easyedapro:SOD-323_L1.8-W1.3-LS2.5-RD")
      (description "Forward Voltage (Vf@If):600mV@1A Reverse Voltage (Vr):40V Average Rectified Current (Io):1A")
      (fields (field (name "Manufacturer") "Hottech(合科泰)"))
      (libsource (lib "easyedapro") (part "1N5819WS"))
    )
    (comp (ref "D270")
      (value "1N5819WS")
      (footprint "easyedapro:SOD-323_L1.8-W1.3-LS2.5-RD")
      (description "Forward Voltage (Vf@If):600mV@1A Reverse Voltage (Vr):40V Average Rectified Current (Io):1A")
      (fields (field (name "Manufacturer") "Hottech(合科泰)"))
      (libsource (lib "easyedapro") (part "1N5819WS"))
    )
    (comp (ref "D271")
      (value "1N5819WS")
      (footprint "easyedapro:SOD-323_L1.8-W1.3-LS2.5-RD")
      (description "Forward Voltage (Vf@If):600mV@1A Reverse Voltage (Vr):40V Average Rectified Current (Io):1A")
      (fields (field (name "Manufacturer") "Hottech(合科泰)"))
      (libsource (lib "easyedapro") (part "1N5819WS"))
    )
    (comp (ref "D272")
      (value "1N5819WS")
      (footprint "easyedapro:SOD-323_L1.8-W1.3-LS2.5-RD")
      (description "Forward Voltage (Vf@If):600mV@1A Reverse Voltage (Vr):40V Average Rectified Current (Io):1A")
      (fields (field (name "Manufacturer") "Hottech(合科泰)"))
      (libsource (lib "easyedapro") (part "1N5819WS"))
    )
    (comp (ref "D273")
      (value "1N5819WS")
      (footprint "easyedapro:SOD-323_L1.8-W1.3-LS2.5-RD")
      (description "Forward Voltage (Vf@If):600mV@1A Reverse Voltage (Vr):40V Average Rectified Current (Io):1A")
      (fields (field (name "Manufacturer") "Hottech(合科泰)"))
      (libsource (lib "easyedapro") (part "1N5819WS"))
    )
    (comp (ref "D274")
      (value "1N5819WS")
      (footprint "easyedapro:SOD-323_L1.8-W1.3-LS2.5-RD")
      (description "Forward Voltage (Vf@If):600mV@1A Reverse Voltage (Vr):40V Average Rectified Current (Io):1A")
      (fields (field (name "Manufacturer") "Hottech(合科泰)"))
      (libsource (lib "easyedapro") (part "1N5819WS"))
    )
    (comp (ref "D275")
      (value "1N5819WS")
      (footprint "easyedapro:SOD-323_L1.8-W1.3-LS2.5-RD")
      (description "Forward Voltage (Vf@If):600mV@1A Reverse Voltage (Vr):40V Average Rectified Current (Io):1A")
      (fields (field (name "Manufacturer") "Hottech(合科泰)"))
      (libsource (lib "easyedapro") (part "1N5819WS"))
    )
    (comp (ref "D276")
      (value "1N5819WS")
      (footprint "easyedapro:SOD-323_L1.8-W1.3-LS2.5-RD")
      (description "Forward Voltage (Vf@If):600mV@1A Reverse Voltage (Vr):40V Average Rectified Current (Io):1A")
      (fields (field (name "Manufacturer") "Hottech(合科泰)"))
      (libsource (lib "easyedapro") (part "1N5819WS"))
    )
    (comp (ref "D277")
      (value "1N5819WS")
      (footprint "easyedapro:SOD-323_L1.8-W1.3-LS2.5-RD")
      (description "Forward Voltage (Vf@If):600mV@1A Reverse Voltage (Vr):40V Average Rectified Current (Io):1A")
      (fields (field (name "Manufacturer") "Hottech(合科泰)"))
      (libsource (lib "easyedapro") (part "1N5819WS"))
    )
    (comp (ref "D278")
      (value "1N5819WS")
      (footprint "easyedapro:SOD-323_L1.8-W1.3-LS2.5-RD")
      (description "Forward Voltage (Vf@If):600mV@1A Reverse Voltage (Vr):40V Average Rectified Current (Io):1A")
      (fields (field (name "Manufacturer") "Hottech(合科泰)"))
      (libsource (lib "easyedapro") (part "1N5819WS"))
    )
    (comp (ref "D279")
      (value "1N5819WS")
      (footprint "easyedapro:SOD-323_L1.8-W1.3-LS2.5-RD")
      (description "Forward Voltage (Vf@If):600mV@1A Reverse Voltage (Vr):40V Average Rectified Current (Io):1A")
      (fields (field (name "Manufacturer") "Hottech(合科泰)"))
      (libsource (lib "easyedapro") (part "1N5819WS"))
    )
    (comp (ref "D280")
      (value "1N5819WS")
      (footprint "easyedapro:SOD-323_L1.8-W1.3-LS2.5-RD")
      (description "Forward Voltage (Vf@If):600mV@1A Reverse Voltage (Vr):40V Average Rectified Current (Io):1A")
      (fields (field (name "Manufacturer") "Hottech(合科泰)"))
      (libsource (lib "easyedapro") (part "1N5819WS"))
    )
    (comp (ref "D281")
      (value "1N5819WS")
      (footprint "easyedapro:SOD-323_L1.8-W1.3-LS2.5-RD")
      (description "Forward Voltage (Vf@If):600mV@1A Reverse Voltage (Vr):40V Average Rectified Current (Io):1A")
      (fields (field (name "Manufacturer") "Hottech(合科泰)"))
      (libsource (lib "easyedapro") (part "1N5819WS"))
    )
    (comp (ref "D282")
      (value "1N5819WS")
      (footprint "easyedapro:SOD-323_L1.8-W1.3-LS2.5-RD")
      (description "Forward Voltage (Vf@If):600mV@1A Reverse Voltage (Vr):40V Average Rectified Current (Io):1A")
      (fields (field (name "Manufacturer") "Hottech(合科泰)"))
      (libsource (lib "easyedapro") (part "1N5819WS"))
    )
    (comp (ref "D283")
      (value "1N5819WS")
      (footprint "easyedapro:SOD-323_L1.8-W1.3-LS2.5-RD")
      (description "Forward Voltage (Vf@If):600mV@1A Reverse Voltage (Vr):40V Average Rectified Current (Io):1A")
      (fields (field (name "Manufacturer") "Hottech(合科泰)"))
      (libsource (lib "easyedapro") (part "1N5819WS"))
    )
    (comp (ref "D284")
      (value "1N5819WS")
      (footprint "easyedapro:SOD-323_L1.8-W1.3-LS2.5-RD")
      (description "Forward Voltage (Vf@If):600mV@1A Reverse Voltage (Vr):40V Average Rectified Current (Io):1A")
      (fields (field (name "Manufacturer") "Hottech(合科泰)"))
      (libsource (lib "easyedapro") (part "1N5819WS"))
    )
    (comp (ref "D285")
      (value "1N5819WS")
      (footprint "easyedapro:SOD-323_L1.8-W1.3-LS2.5-RD")
      (description "Forward Voltage (Vf@If):600mV@1A Reverse Voltage (Vr):40V Average Rectified Current (Io):1A")
      (fields (field (name "Manufacturer") "Hottech(合科泰)"))
      (libsource (lib "easyedapro") (part "1N5819WS"))
    )
    (comp (ref "D286")
      (value "1N5819WS")
      (footprint "easyedapro:SOD-323_L1.8-W1.3-LS2.5-RD")
      (description "Forward Voltage (Vf@If):600mV@1A Reverse Voltage (Vr):40V Average Rectified Current (Io):1A")
      (fields (field (name "Manufacturer") "Hottech(合科泰)"))
      (libsource (lib "easyedapro") (part "1N5819WS"))
    )
    (comp (ref "D287")
      (value "1N5819WS")
      (footprint "easyedapro:SOD-323_L1.8-W1.3-LS2.5-RD")
      (description "Forward Voltage (Vf@If):600mV@1A Reverse Voltage (Vr):40V Average Rectified Current (Io):1A")
      (fields (field (name "Manufacturer") "Hottech(合科泰)"))
      (libsource (lib "easyedapro") (part "1N5819WS"))
    )
    (comp (ref "D288")
      (value "1N5819WS")
      (footprint "easyedapro:SOD-323_L1.8-W1.3-LS2.5-RD")
      (description "Forward Voltage (Vf@If):600mV@1A Reverse Voltage (Vr):40V Average Rectified Current (Io):1A")
      (fields (field (name "Manufacturer") "Hottech(合科泰)"))
      (libsource (lib "easyedapro") (part "1N5819WS"))
    )
    (comp (ref "D289")
      (value "1N5819WS")
      (footprint "easyedapro:SOD-323_L1.8-W1.3-LS2.5-RD")
      (description "Forward Voltage (Vf@If):600mV@1A Reverse Voltage (Vr):40V Average Rectified Current (Io):1A")
      (fields (field (name "Manufacturer") "Hottech(合科泰)"))
      (libsource (lib "easyedapro") (part "1N5819WS"))
    )
    (comp (ref "D290")
      (value "1N5819WS")
      (footprint "easyedapro:SOD-323_L1.8-W1.3-LS2.5-RD")
      (description "Forward Voltage (Vf@If):600mV@1A Reverse Voltage (Vr):40V Average Rectified Current (Io):1A")
      (fields (field (name "Manufacturer") "Hottech(合科泰)"))
      (libsource (lib "easyedapro") (part "1N5819WS"))
    )
    (comp (ref "ENC201")
      (value "PEC12R-4120F-S0012")
      (footprint "easyedapro:SW-TH_PEC12R-4120F-S0012_1")
      (fields (field (name "Manufacturer") "BOURNS"))
      (libsource (lib "easyedapro") (part "PEC12R-4120F-S0012_RF_v1.0"))
    )
    (comp (ref "FPC1")
      (value "FH28-10S-0.5SH(05)")
      (footprint "easyedapro:FFC-SMD_10P-P0.50_FH28-10S-0.5SH-05")
      (fields (field (name "Manufacturer") "HRS(广濑)"))
      (libsource (lib "easyedapro") (part "FH28-10S-0.5SH(05)"))
    )
    (comp (ref "J201")
      (value "CPG151101S11-16")
      (footprint "easyedapro:SMD_KEYBOARD-SW_1")
      (fields (field (name "Manufacturer") "Kailh(凯华)"))
      (libsource (lib "easyedapro") (part "CPG151101S11-16_RF_v1.0"))
    )
    (comp (ref "J202")
      (value "CPG151101S11-16")
      (footprint "easyedapro:SMD_KEYBOARD-SW_1")
      (fields (field (name "Manufacturer") "Kailh(凯华)"))
      (libsource (lib "easyedapro") (part "CPG151101S11-16_RF_v1.0"))
    )
    (comp (ref "J203")
      (value "CPG151101S11-16")
      (footprint "easyedapro:SMD_KEYBOARD-SW_1")
      (fields (field (name "Manufacturer") "Kailh(凯华)"))
      (libsource (lib "easyedapro") (part "CPG151101S11-16_RF_v1.0"))
    )
    (comp (ref "J204")
      (value "CPG151101S11-16")
      (footprint "easyedapro:SMD_KEYBOARD-SW_1")
      (fields (field (name "Manufacturer") "Kailh(凯华)"))
      (libsource (lib "easyedapro") (part "CPG151101S11-16_RF_v1.0"))
    )
    (comp (ref "J205")
      (value "CPG151101S11-16")
      (footprint "easyedapro:SMD_KEYBOARD-SW_1")
      (fields (field (name "Manufacturer") "Kailh(凯华)"))
      (libsource (lib "easyedapro") (part "CPG151101S11-16_RF_v1.0"))
    )
    (comp (ref "J206")
      (value "CPG151101S11-16")
      (footprint "easyedapro:SMD_KEYBOARD-SW_1")
      (fields (field (name "Manufacturer") "Kailh(凯华)"))
      (libsource (lib "easyedapro") (part "CPG151101S11-16_RF_v1.0"))
    )
    (comp (ref "J207")
      (value "CPG151101S11-16")
      (footprint "easyedapro:SMD_KEYBOARD-SW_1")
      (fields (field (name "Manufacturer") "Kailh(凯华)"))
      (libsource (lib "easyedapro") (part "CPG151101S11-16_RF_v1.0"))
    )
    (comp (ref "J208")
      (value "CPG151101S11-16")
      (footprint "easyedapro:SMD_KEYBOARD-SW_1")
      (fields (field (name "Manufacturer") "Kailh(凯华)"))
      (libsource (lib "easyedapro") (part "CPG151101S11-16_RF_v1.0"))
    )
    (comp (ref "J209")
      (value "CPG151101S11-16")
      (footprint "easyedapro:SMD_KEYBOARD-SW_1")
      (fields (field (name "Manufacturer") "Kailh(凯华)"))
      (libsource (lib "easyedapro") (part "CPG151101S11-16_RF_v1.0"))
    )
    (comp (ref "J210")
      (value "CPG151101S11-16")
      (footprint "easyedapro:SMD_KEYBOARD-SW_1")
      (fields (field (name "Manufacturer") "Kailh(凯华)"))
      (libsource (lib "easyedapro") (part "CPG151101S11-16_RF_v1.0"))
    )
    (comp (ref "J211")
      (value "CPG151101S11-16")
      (footprint "easyedapro:SMD_KEYBOARD-SW_1")
      (fields (field (name "Manufacturer") "Kailh(凯华)"))
      (libsource (lib "easyedapro") (part "CPG151101S11-16_RF_v1.0"))
    )
    (comp (ref "J212")
      (value "CPG151101S11-16")
      (footprint "easyedapro:SMD_KEYBOARD-SW_1")
      (fields (field (name "Manufacturer") "Kailh(凯华)"))
      (libsource (lib "easyedapro") (part "CPG151101S11-16_RF_v1.0"))
    )
    (comp (ref "J213")
      (value "CPG151101S11-16")
      (footprint "easyedapro:SMD_KEYBOARD-SW_1")
      (fields (field (name "Manufacturer") "Kailh(凯华)"))
      (libsource (lib "easyedapro") (part "CPG151101S11-16_RF_v1.0"))
    )
    (comp (ref "J214")
      (value "CPG151101S11-16")
      (footprint "easyedapro:SMD_KEYBOARD-SW_1")
      (fields (field (name "Manufacturer") "Kailh(凯华)"))
      (libsource (lib "easyedapro") (part "CPG151101S11-16_RF_v1.0"))
    )
    (comp (ref "J215")
      (value "CPG151101S11-16")
      (footprint "easyedapro:SMD_KEYBOARD-SW_1")
      (fields (field (name "Manufacturer") "Kailh(凯华)"))
      (libsource (lib "easyedapro") (part "CPG151101S11-16_RF_v1.0"))
    )
    (comp (ref "J216")
      (value "CPG151101S11-16")
      (footprint "easyedapro:SMD_KEYBOARD-SW_1")
      (fields (field (name "Manufacturer") "Kailh(凯华)"))
      (libsource (lib "easyedapro") (part "CPG151101S11-16_RF_v1.0"))
    )
    (comp (ref "J217")
      (value "CPG151101S11-16")
      (footprint "easyedapro:SMD_KEYBOARD-SW_1")
      (fields (field (name "Manufacturer") "Kailh(凯华)"))
      (libsource (lib "easyedapro") (part "CPG151101S11-16_RF_v1.0"))
    )
    (comp (ref "J218")
      (value "CPG151101S11-16")
      (footprint "easyedapro:SMD_KEYBOARD-SW_1")
      (fields (field (name "Manufacturer") "Kailh(凯华)"))
      (libsource (lib "easyedapro") (part "CPG151101S11-16_RF_v1.0"))
    )
    (comp (ref "J219")
      (value "CPG151101S11-16")
      (footprint "easyedapro:SMD_KEYBOARD-SW_1")
      (fields (field (name "Manufacturer") "Kailh(凯华)"))
      (libsource (lib "easyedapro") (part "CPG151101S11-16_RF_v1.0"))
    )
    (comp (ref "J220")
      (value "CPG151101S11-16")
      (footprint "easyedapro:SMD_KEYBOARD-SW_1")
      (fields (field (name "Manufacturer") "Kailh(凯华)"))
      (libsource (lib "easyedapro") (part "CPG151101S11-16_RF_v1.0"))
    )
    (comp (ref "J221")
      (value "CPG151101S11-16")
      (footprint "easyedapro:SMD_KEYBOARD-SW_1")
      (fields (field (name "Manufacturer") "Kailh(凯华)"))
      (libsource (lib "easyedapro") (part "CPG151101S11-16_RF_v1.0"))
    )
    (comp (ref "J222")
      (value "CPG151101S11-16")
      (footprint "easyedapro:SMD_KEYBOARD-SW_1")
      (fields (field (name "Manufacturer") "Kailh(凯华)"))
      (libsource (lib "easyedapro") (part "CPG151101S11-16_RF_v1.0"))
    )
    (comp (ref "J223")
      (value "CPG151101S11-16")
      (footprint "easyedapro:SMD_KEYBOARD-SW_1")
      (fields (field (name "Manufacturer") "Kailh(凯华)"))
      (libsource (lib "easyedapro") (part "CPG151101S11-16_RF_v1.0"))
    )
    (comp (ref "J224")
      (value "CPG151101S11-16")
      (footprint "easyedapro:SMD_KEYBOARD-SW_1")
      (fields (field (name "Manufacturer") "Kailh(凯华)"))
      (libsource (lib "easyedapro") (part "CPG151101S11-16_RF_v1.0"))
    )
    (comp (ref "J225")
      (value "CPG151101S11-16")
      (footprint "easyedapro:SMD_KEYBOARD-SW_1")
      (fields (field (name "Manufacturer") "Kailh(凯华)"))
      (libsource (lib "easyedapro") (part "CPG151101S11-16_RF_v1.0"))
    )
    (comp (ref "J226")
      (value "CPG151101S11-16")
      (footprint "easyedapro:SMD_KEYBOARD-SW_1")
      (fields (field (name "Manufacturer") "Kailh(凯华)"))
      (libsource (lib "easyedapro") (part "CPG151101S11-16_RF_v1.0"))
    )
    (comp (ref "J227")
      (value "CPG151101S11-16")
      (footprint "easyedapro:SMD_KEYBOARD-SW_1")
      (fields (field (name "Manufacturer") "Kailh(凯华)"))
      (libsource (lib "easyedapro") (part "CPG151101S11-16_RF_v1.0"))
    )
    (comp (ref "J228")
      (value "CPG151101S11-16")
      (footprint "easyedapro:SMD_KEYBOARD-SW_1")
      (fields (field (name "Manufacturer") "Kailh(凯华)"))
      (libsource (lib "easyedapro") (part "CPG151101S11-16_RF_v1.0"))
    )
    (comp (ref "J229")
      (value "CPG151101S11-16")
      (footprint "easyedapro:SMD_KEYBOARD-SW_1")
      (fields (field (name "Manufacturer") "Kailh(凯华)"))
      (libsource (lib "easyedapro") (part "CPG151101S11-16_RF_v1.0"))
    )
    (comp (ref "J230")
      (value "CPG151101S11-16")
      (footprint "easyedapro:SMD_KEYBOARD-SW_1")
      (fields (field (name "Manufacturer") "Kailh(凯华)"))
      (libsource (lib "easyedapro") (part "CPG151101S11-16_RF_v1.0"))
    )
    (comp (ref "J231")
      (value "CPG151101S11-16")
      (footprint "easyedapro:SMD_KEYBOARD-SW_1")
      (fields (field (name "Manufacturer") "Kailh(凯华)"))
      (libsource (lib "easyedapro") (part "CPG151101S11-16_RF_v1.0"))
    )
    (comp (ref "J232")
      (value "CPG151101S11-16")
      (footprint "easyedapro:SMD_KEYBOARD-SW_1")
      (fields (field (name "Manufacturer") "Kailh(凯华)"))
      (libsource (lib "easyedapro") (part "CPG151101S11-16_RF_v1.0"))
    )
    (comp (ref "J233")
      (value "CPG151101S11-16")
      (footprint "easyedapro:SMD_KEYBOARD-SW_1")
      (fields (field (name "Manufacturer") "Kailh(凯华)"))
      (libsource (lib "easyedapro") (part "CPG151101S11-16_RF_v1.0"))
    )
    (comp (ref "J234")
      (value "CPG151101S11-16")
      (footprint "easyedapro:SMD_KEYBOARD-SW_1")
      (fields (field (name "Manufacturer") "Kailh(凯华)"))
      (libsource (lib "easyedapro") (part "CPG151101S11-16_RF_v1.0"))
    )
    (comp (ref "J235")
      (value "CPG151101S11-16")
      (footprint "easyedapro:SMD_KEYBOARD-SW_1")
      (fields (field (name "Manufacturer") "Kailh(凯华)"))
      (libsource (lib "easyedapro") (part "CPG151101S11-16_RF_v1.0"))
    )
    (comp (ref "J236")
      (value "CPG151101S11-16")
      (footprint "easyedapro:SMD_KEYBOARD-SW_1")
      (fields (field (name "Manufacturer") "Kailh(凯华)"))
      (libsource (lib "easyedapro") (part "CPG151101S11-16_RF_v1.0"))
    )
    (comp (ref "J237")
      (value "CPG151101S11-16")
      (footprint "easyedapro:SMD_KEYBOARD-SW_1")
      (fields (field (name "Manufacturer") "Kailh(凯华)"))
      (libsource (lib "easyedapro") (part "CPG151101S11-16_RF_v1.0"))
    )
    (comp (ref "J238")
      (value "CPG151101S11-16")
      (footprint "easyedapro:SMD_KEYBOARD-SW_1")
      (fields (field (name "Manufacturer") "Kailh(凯华)"))
      (libsource (lib "easyedapro") (part "CPG151101S11-16_RF_v1.0"))
    )
    (comp (ref "J239")
      (value "CPG151101S11-16")
      (footprint "easyedapro:SMD_KEYBOARD-SW_1")
      (fields (field (name "Manufacturer") "Kailh(凯华)"))
      (libsource (lib "easyedapro") (part "CPG151101S11-16_RF_v1.0"))
    )
    (comp (ref "J240")
      (value "CPG151101S11-16")
      (footprint "easyedapro:SMD_KEYBOARD-SW_1")
      (fields (field (name "Manufacturer") "Kailh(凯华)"))
      (libsource (lib "easyedapro") (part "CPG151101S11-16_RF_v1.0"))
    )
    (comp (ref "J241")
      (value "CPG151101S11-16")
      (footprint "easyedapro:SMD_KEYBOARD-SW_1")
      (fields (field (name "Manufacturer") "Kailh(凯华)"))
      (libsource (lib "easyedapro") (part "CPG151101S11-16_RF_v1.0"))
    )
    (comp (ref "J242")
      (value "CPG151101S11-16")
      (footprint "easyedapro:SMD_KEYBOARD-SW_1")
      (fields (field (name "Manufacturer") "Kailh(凯华)"))
      (libsource (lib "easyedapro") (part "CPG151101S11-16_RF_v1.0"))
    )
    (comp (ref "J243")
      (value "CPG151101S11-16")
      (footprint "easyedapro:SMD_KEYBOARD-SW_1")
      (fields (field (name "Manufacturer") "Kailh(凯华)"))
      (libsource (lib "easyedapro") (part "CPG151101S11-16_RF_v1.0"))
    )
    (comp (ref "J244")
      (value "CPG151101S11-16")
      (footprint "easyedapro:SMD_KEYBOARD-SW_1")
      (fields (field (name "Manufacturer") "Kailh(凯华)"))
      (libsource (lib "easyedapro") (part "CPG151101S11-16_RF_v1.0"))
    )
    (comp (ref "J245")
      (value "CPG151101S11-16")
      (footprint "easyedapro:SMD_KEYBOARD-SW_1")
      (fields (field (name "Manufacturer") "Kailh(凯华)"))
      (libsource (lib "easyedapro") (part "CPG151101S11-16_RF_v1.0"))
    )
    (comp (ref "J246")
      (value "CPG151101S11-16")
      (footprint "easyedapro:SMD_KEYBOARD-SW_1")
      (fields (field (name "Manufacturer") "Kailh(凯华)"))
      (libsource (lib "easyedapro") (part "CPG151101S11-16_RF_v1.0"))
    )
    (comp (ref "J247")
      (value "CPG151101S11-16")
      (footprint "easyedapro:SMD_KEYBOARD-SW_1")
      (fields (field (name "Manufacturer") "Kailh(凯华)"))
      (libsource (lib "easyedapro") (part "CPG151101S11-16_RF_v1.0"))
    )
    (comp (ref "J248")
      (value "CPG151101S11-16")
      (footprint "easyedapro:SMD_KEYBOARD-SW_1")
      (fields (field (name "Manufacturer") "Kailh(凯华)"))
      (libsource (lib "easyedapro") (part "CPG151101S11-16_RF_v1.0"))
    )
    (comp (ref "J249")
      (value "CPG151101S11-16")
      (footprint "easyedapro:SMD_KEYBOARD-SW_1")
      (fields (field (name "Manufacturer") "Kailh(凯华)"))
      (libsource (lib "easyedapro") (part "CPG151101S11-16_RF_v1.0"))
    )
    (comp (ref "J250")
      (value "CPG151101S11-16")
      (footprint "easyedapro:SMD_KEYBOARD-SW_1")
      (fields (field (name "Manufacturer") "Kailh(凯华)"))
      (libsource (lib "easyedapro") (part "CPG151101S11-16_RF_v1.0"))
    )
    (comp (ref "J251")
      (value "CPG151101S11-16")
      (footprint "easyedapro:SMD_KEYBOARD-SW_1")
      (fields (field (name "Manufacturer") "Kailh(凯华)"))
      (libsource (lib "easyedapro") (part "CPG151101S11-16_RF_v1.0"))
    )
    (comp (ref "J252")
      (value "CPG151101S11-16")
      (footprint "easyedapro:SMD_KEYBOARD-SW_1")
      (fields (field (name "Manufacturer") "Kailh(凯华)"))
      (libsource (lib "easyedapro") (part "CPG151101S11-16_RF_v1.0"))
    )
    (comp (ref "J253")
      (value "CPG151101S11-16")
      (footprint "easyedapro:SMD_KEYBOARD-SW_1")
      (fields (field (name "Manufacturer") "Kailh(凯华)"))
      (libsource (lib "easyedapro") (part "CPG151101S11-16_RF_v1.0"))
    )
    (comp (ref "J254")
      (value "CPG151101S11-16")
      (footprint "easyedapro:SMD_KEYBOARD-SW_1")
      (fields (field (name "Manufacturer") "Kailh(凯华)"))
      (libsource (lib "easyedapro") (part "CPG151101S11-16_RF_v1.0"))
    )
    (comp (ref "J255")
      (value "CPG151101S11-16")
      (footprint "easyedapro:SMD_KEYBOARD-SW_1")
      (fields (field (name "Manufacturer") "Kailh(凯华)"))
      (libsource (lib "easyedapro") (part "CPG151101S11-16_RF_v1.0"))
    )
    (comp (ref "J256")
      (value "CPG151101S11-16")
      (footprint "easyedapro:SMD_KEYBOARD-SW_1")
      (fields (field (name "Manufacturer") "Kailh(凯华)"))
      (libsource (lib "easyedapro") (part "CPG151101S11-16_RF_v1.0"))
    )
    (comp (ref "J257")
      (value "CPG151101S11-16")
      (footprint "easyedapro:SMD_KEYBOARD-SW_1")
      (fields (field (name "Manufacturer") "Kailh(凯华)"))
      (libsource (lib "easyedapro") (part "CPG151101S11-16_RF_v1.0"))
    )
    (comp (ref "J258")
      (value "CPG151101S11-16")
      (footprint "easyedapro:SMD_KEYBOARD-SW_1")
      (fields (field (name "Manufacturer") "Kailh(凯华)"))
      (libsource (lib "easyedapro") (part "CPG151101S11-16_RF_v1.0"))
    )
    (comp (ref "J259")
      (value "CPG151101S11-16")
      (footprint "easyedapro:SMD_KEYBOARD-SW_1")
      (fields (field (name "Manufacturer") "Kailh(凯华)"))
      (libsource (lib "easyedapro") (part "CPG151101S11-16_RF_v1.0"))
    )
    (comp (ref "J260")
      (value "CPG151101S11-16")
      (footprint "easyedapro:SMD_KEYBOARD-SW_1")
      (fields (field (name "Manufacturer") "Kailh(凯华)"))
      (libsource (lib "easyedapro") (part "CPG151101S11-16_RF_v1.0"))
    )
    (comp (ref "J261")
      (value "CPG151101S11-16")
      (footprint "easyedapro:SMD_KEYBOARD-SW_1")
      (fields (field (name "Manufacturer") "Kailh(凯华)"))
      (libsource (lib "easyedapro") (part "CPG151101S11-16_RF_v1.0"))
    )
    (comp (ref "J262")
      (value "CPG151101S11-16")
      (footprint "easyedapro:SMD_KEYBOARD-SW_1")
      (fields (field (name "Manufacturer") "Kailh(凯华)"))
      (libsource (lib "easyedapro") (part "CPG151101S11-16_RF_v1.0"))
    )
    (comp (ref "J263")
      (value "CPG151101S11-16")
      (footprint "easyedapro:SMD_KEYBOARD-SW_1")
      (fields (field (name "Manufacturer") "Kailh(凯华)"))
      (libsource (lib "easyedapro") (part "CPG151101S11-16_RF_v1.0"))
    )
    (comp (ref "J264")
      (value "CPG151101S11-16")
      (footprint "easyedapro:SMD_KEYBOARD-SW_1")
      (fields (field (name "Manufacturer") "Kailh(凯华)"))
      (libsource (lib "easyedapro") (part "CPG151101S11-16_RF_v1.0"))
    )
    (comp (ref "J265")
      (value "CPG151101S11-16")
      (footprint "easyedapro:SMD_KEYBOARD-SW_1")
      (fields (field (name "Manufacturer") "Kailh(凯华)"))
      (libsource (lib "easyedapro") (part "CPG151101S11-16_RF_v1.0"))
    )
    (comp (ref "J266")
      (value "CPG151101S11-16")
      (footprint "easyedapro:SMD_KEYBOARD-SW_1")
      (fields (field (name "Manufacturer") "Kailh(凯华)"))
      (libsource (lib "easyedapro") (part "CPG151101S11-16_RF_v1.0"))
    )
    (comp (ref "J267")
      (value "CPG151101S11-16")
      (footprint "easyedapro:SMD_KEYBOARD-SW_1")
      (fields (field (name "Manufacturer") "Kailh(凯华)"))
      (libsource (lib "easyedapro") (part "CPG151101S11-16_RF_v1.0"))
    )
    (comp (ref "J268")
      (value "CPG151101S11-16")
      (footprint "easyedapro:SMD_KEYBOARD-SW_1")
      (fields (field (name "Manufacturer") "Kailh(凯华)"))
      (libsource (lib "easyedapro") (part "CPG151101S11-16_RF_v1.0"))
    )
    (comp (ref "J269")
      (value "CPG151101S11-16")
      (footprint "easyedapro:SMD_KEYBOARD-SW_1")
      (fields (field (name "Manufacturer") "Kailh(凯华)"))
      (libsource (lib "easyedapro") (part "CPG151101S11-16_RF_v1.0"))
    )
    (comp (ref "J270")
      (value "CPG151101S11-16")
      (footprint "easyedapro:SMD_KEYBOARD-SW_1")
      (fields (field (name "Manufacturer") "Kailh(凯华)"))
      (libsource (lib "easyedapro") (part "CPG151101S11-16_RF_v1.0"))
    )
    (comp (ref "J271")
      (value "CPG151101S11-16")
      (footprint "easyedapro:SMD_KEYBOARD-SW_1")
      (fields (field (name "Manufacturer") "Kailh(凯华)"))
      (libsource (lib "easyedapro") (part "CPG151101S11-16_RF_v1.0"))
    )
    (comp (ref "J272")
      (value "CPG151101S11-16")
      (footprint "easyedapro:SMD_KEYBOARD-SW_1")
      (fields (field (name "Manufacturer") "Kailh(凯华)"))
      (libsource (lib "easyedapro") (part "CPG151101S11-16_RF_v1.0"))
    )
    (comp (ref "J273")
      (value "CPG151101S11-16")
      (footprint "easyedapro:SMD_KEYBOARD-SW_1")
      (fields (field (name "Manufacturer") "Kailh(凯华)"))
      (libsource (lib "easyedapro") (part "CPG151101S11-16_RF_v1.0"))
    )
    (comp (ref "J274")
      (value "CPG151101S11-16")
      (footprint "easyedapro:SMD_KEYBOARD-SW_1")
      (fields (field (name "Manufacturer") "Kailh(凯华)"))
      (libsource (lib "easyedapro") (part "CPG151101S11-16_RF_v1.0"))
    )
    (comp (ref "J275")
      (value "CPG151101S11-16")
      (footprint "easyedapro:SMD_KEYBOARD-SW_1")
      (fields (field (name "Manufacturer") "Kailh(凯华)"))
      (libsource (lib "easyedapro") (part "CPG151101S11-16_RF_v1.0"))
    )
    (comp (ref "J276")
      (value "CPG151101S11-16")
      (footprint "easyedapro:SMD_KEYBOARD-SW_1")
      (fields (field (name "Manufacturer") "Kailh(凯华)"))
      (libsource (lib "easyedapro") (part "CPG151101S11-16_RF_v1.0"))
    )
    (comp (ref "J277")
      (value "CPG151101S11-16")
      (footprint "easyedapro:SMD_KEYBOARD-SW_1")
      (fields (field (name "Manufacturer") "Kailh(凯华)"))
      (libsource (lib "easyedapro") (part "CPG151101S11-16_RF_v1.0"))
    )
    (comp (ref "J278")
      (value "CPG151101S11-16")
      (footprint "easyedapro:SMD_KEYBOARD-SW_1")
      (fields (field (name "Manufacturer") "Kailh(凯华)"))
      (libsource (lib "easyedapro") (part "CPG151101S11-16_RF_v1.0"))
    )
    (comp (ref "MH201")
      (value "STANDOFF_M2.5x3.5MM")
      (footprint "easyedapro:STANDOFF_M2.5x3.5MM_RF_v1.0")
      (description "Standoff, Steel, M2.5, Hex Female-Female, 3.5 mm, 4.9 mm, WA-SMSI Series")
      (fields (field (name "Manufacturer") "WURTH ELEKTRONIK"))
      (libsource (lib "easyedapro") (part "9774035151R_RF_v1.0"))
    )
    (comp (ref "MH202")
      (value "STANDOFF_M2.5x3.5MM")
      (footprint "easyedapro:STANDOFF_M2.5x3.5MM_RF_v1.0")
      (description "Standoff, Steel, M2.5, Hex Female-Female, 3.5 mm, 4.9 mm, WA-SMSI Series")
      (fields (field (name "Manufacturer") "WURTH ELEKTRONIK"))
      (libsource (lib "easyedapro") (part "9774035151R_RF_v1.0"))
    )
    (comp (ref "MH203")
      (value "STANDOFF_M2.5x3.5MM")
      (footprint "easyedapro:STANDOFF_M2.5x3.5MM_RF_v1.0")
      (description "Standoff, Steel, M2.5, Hex Female-Female, 3.5 mm, 4.9 mm, WA-SMSI Series")
      (fields (field (name "Manufacturer") "WURTH ELEKTRONIK"))
      (libsource (lib "easyedapro") (part "9774035151R_RF_v1.0"))
    )
    (comp (ref "MH204")
      (value "STANDOFF_M2.5x3.5MM")
      (footprint "easyedapro:STANDOFF_M2.5x3.5MM_RF_v1.0")
      (description "Standoff, Steel, M2.5, Hex Female-Female, 3.5 mm, 4.9 mm, WA-SMSI Series")
      (fields (field (name "Manufacturer") "WURTH ELEKTRONIK"))
      (libsource (lib "easyedapro") (part "9774035151R_RF_v1.0"))
    )
    (comp (ref "MH205")
      (value "~")
      (footprint "easyedapro:MH_7.5X3.2MM_RF_v1.0")
      (libsource (lib "easyedapro") (part "MH_7.5X3.2MM_RF_v1.0"))
    )
    (comp (ref "MH206")
      (value "~")
      (footprint "easyedapro:MH_7.5X3.2MM_RF_v1.0")
      (libsource (lib "easyedapro") (part "MH_7.5X3.2MM_RF_v1.0"))
    )
    (comp (ref "MH207")
      (value "~")
      (footprint "easyedapro:MH_7.5X3.2MM_RF_v1.0")
      (libsource (lib "easyedapro") (part "MH_7.5X3.2MM_RF_v1.0"))
    )
    (comp (ref "MH208")
      (value "~")
      (footprint "easyedapro:MH_7.5X3.2MM_RF_v1.0")
      (libsource (lib "easyedapro") (part "MH_7.5X3.2MM_RF_v1.0"))
    )
    (comp (ref "R201")
      (value "10kΩ")
      (footprint "easyedapro:R0402")
      (fields
        (field (name "Manufacturer Part") "0402WGF1002TCE")
        (field (name "Manufacturer") "UNI-ROYAL(厚声)")
      )
      (libsource (lib "easyedapro") (part "0402WGF1002TCE"))
    )
    (comp (ref "R202")
      (value "10kΩ")
      (footprint "easyedapro:R0402")
      (fields
        (field (name "Manufacturer Part") "0402WGF1002TCE")
        (field (name "Manufacturer") "UNI-ROYAL(厚声)")
      )
      (libsource (lib "easyedapro") (part "0402WGF1002TCE"))
    )
    (comp (ref "R205")
      (value "10kΩ")
      (footprint "easyedapro:R0402")
      (fields
        (field (name "Manufacturer Part") "0402WGF1002TCE")
        (field (name "Manufacturer") "UNI-ROYAL(厚声)")
      )
      (libsource (lib "easyedapro") (part "0402WGF1002TCE"))
    )
    (comp (ref "R207")
      (value "10kΩ")
      (footprint "easyedapro:R0402")
      (fields
        (field (name "Manufacturer Part") "0402WGF1002TCE")
        (field (name "Manufacturer") "UNI-ROYAL(厚声)")
      )
      (libsource (lib "easyedapro") (part "0402WGF1002TCE"))
    )
    (comp (ref "R223")
      (value "10kΩ")
      (footprint "easyedapro:R0402")
      (fields
        (field (name "Manufacturer Part") "0402WGF1002TCE")
        (field (name "Manufacturer") "UNI-ROYAL(厚声)")
      )
      (libsource (lib "easyedapro") (part "0402WGF1002TCE"))
    )
    (comp (ref "R224")
      (value "10kΩ")
      (footprint "easyedapro:R0402")
      (fields
        (field (name "Manufacturer Part") "0402WGF1002TCE")
        (field (name "Manufacturer") "UNI-ROYAL(厚声)")
      )
      (libsource (lib "easyedapro") (part "0402WGF1002TCE"))
    )
    (comp (ref "SW201")
      (value "CPG151101S21")
      (footprint "easyedapro:KEY-TH_CPG1511F01S0X_1")
      (fields (field (name "Manufacturer") "Kailh(凯华)"))
      (libsource (lib "easyedapro") (part "CPG151101S21 RF v1.0"))
    )
    (comp (ref "SW202")
      (value "CPG151101S21")
      (footprint "easyedapro:KEY-TH_CPG1511F01S0X_1")
      (fields (field (name "Manufacturer") "Kailh(凯华)"))
      (libsource (lib "easyedapro") (part "CPG151101S21 RF v1.0"))
    )
    (comp (ref "SW203")
      (value "CPG151101S21")
      (footprint "easyedapro:KEY-TH_CPG1511F01S0X_1")
      (fields (field (name "Manufacturer") "Kailh(凯华)"))
      (libsource (lib "easyedapro") (part "CPG151101S21 RF v1.0"))
    )
    (comp (ref "SW204")
      (value "CPG151101S21")
      (footprint "easyedapro:KEY-TH_CPG1511F01S0X_1")
      (fields (field (name "Manufacturer") "Kailh(凯华)"))
      (libsource (lib "easyedapro") (part "CPG151101S21 RF v1.0"))
    )
    (comp (ref "SW205")
      (value "CPG151101S21")
      (footprint "easyedapro:KEY-TH_CPG1511F01S0X_1")
      (fields (field (name "Manufacturer") "Kailh(凯华)"))
      (libsource (lib "easyedapro") (part "CPG151101S21 RF v1.0"))
    )
    (comp (ref "SW206")
      (value "CPG151101S21")
      (footprint "easyedapro:KEY-TH_CPG1511F01S0X_1")
      (fields (field (name "Manufacturer") "Kailh(凯华)"))
      (libsource (lib "easyedapro") (part "CPG151101S21 RF v1.0"))
    )
    (comp (ref "SW207")
      (value "CPG151101S21")
      (footprint "easyedapro:KEY-TH_CPG1511F01S0X_1")
      (fields (field (name "Manufacturer") "Kailh(凯华)"))
      (libsource (lib "easyedapro") (part "CPG151101S21 RF v1.0"))
    )
    (comp (ref "SW208")
      (value "CPG151101S21")
      (footprint "easyedapro:KEY-TH_CPG1511F01S0X_1")
      (fields (field (name "Manufacturer") "Kailh(凯华)"))
      (libsource (lib "easyedapro") (part "CPG151101S21 RF v1.0"))
    )
    (comp (ref "SW209")
      (value "CPG151101S21")
      (footprint "easyedapro:KEY-TH_CPG1511F01S0X_1")
      (fields (field (name "Manufacturer") "Kailh(凯华)"))
      (libsource (lib "easyedapro") (part "CPG151101S21 RF v1.0"))
    )
    (comp (ref "SW210")
      (value "CPG151101S21")
      (footprint "easyedapro:KEY-TH_CPG1511F01S0X_1")
      (fields (field (name "Manufacturer") "Kailh(凯华)"))
      (libsource (lib "easyedapro") (part "CPG151101S21 RF v1.0"))
    )
    (comp (ref "SW211")
      (value "CPG151101S21")
      (footprint "easyedapro:KEY-TH_CPG1511F01S0X_1")
      (fields (field (name "Manufacturer") "Kailh(凯华)"))
      (libsource (lib "easyedapro") (part "CPG151101S21 RF v1.0"))
    )
    (comp (ref "SW212")
      (value "CPG151101S21")
      (footprint "easyedapro:KEY-TH_CPG1511F01S0X_1")
      (fields (field (name "Manufacturer") "Kailh(凯华)"))
      (libsource (lib "easyedapro") (part "CPG151101S21 RF v1.0"))
    )
    (comp (ref "SW213")
      (value "CPG151101S21")
      (footprint "easyedapro:KEY-TH_CPG1511F01S0X_1")
      (fields (field (name "Manufacturer") "Kailh(凯华)"))
      (libsource (lib "easyedapro") (part "CPG151101S21 RF v1.0"))
    )
    (comp (ref "SW214")
      (value "CPG151101S21")
      (footprint "easyedapro:KEY-TH_CPG1511F01S0X_1")
      (fields (field (name "Manufacturer") "Kailh(凯华)"))
      (libsource (lib "easyedapro") (part "CPG151101S21 RF v1.0"))
    )
    (comp (ref "SW215")
      (value "CPG151101S21")
      (footprint "easyedapro:KEY-TH_CPG1511F01S0X_1")
      (fields (field (name "Manufacturer") "Kailh(凯华)"))
      (libsource (lib "easyedapro") (part "CPG151101S21 RF v1.0"))
    )
    (comp (ref "SW216")
      (value "CPG151101S21")
      (footprint "easyedapro:KEY-TH_CPG1511F01S0X_1")
      (fields (field (name "Manufacturer") "Kailh(凯华)"))
      (libsource (lib "easyedapro") (part "CPG151101S21 RF v1.0"))
    )
    (comp (ref "SW217")
      (value "CPG151101S21")
      (footprint "easyedapro:KEY-TH_CPG1511F01S0X_1")
      (fields (field (name "Manufacturer") "Kailh(凯华)"))
      (libsource (lib "easyedapro") (part "CPG151101S21 RF v1.0"))
    )
    (comp (ref "SW218")
      (value "CPG151101S21")
      (footprint "easyedapro:KEY-TH_CPG1511F01S0X_1")
      (fields (field (name "Manufacturer") "Kailh(凯华)"))
      (libsource (lib "easyedapro") (part "CPG151101S21 RF v1.0"))
    )
    (comp (ref "SW219")
      (value "CPG151101S21")
      (footprint "easyedapro:KEY-TH_CPG1511F01S0X_1")
      (fields (field (name "Manufacturer") "Kailh(凯华)"))
      (libsource (lib "easyedapro") (part "CPG151101S21 RF v1.0"))
    )
    (comp (ref "SW220")
      (value "CPG151101S21")
      (footprint "easyedapro:KEY-TH_CPG1511F01S0X_1")
      (fields (field (name "Manufacturer") "Kailh(凯华)"))
      (libsource (lib "easyedapro") (part "CPG151101S21 RF v1.0"))
    )
    (comp (ref "SW221")
      (value "CPG151101S21")
      (footprint "easyedapro:KEY-TH_CPG1511F01S0X_1")
      (fields (field (name "Manufacturer") "Kailh(凯华)"))
      (libsource (lib "easyedapro") (part "CPG151101S21 RF v1.0"))
    )
    (comp (ref "SW222")
      (value "CPG151101S21")
      (footprint "easyedapro:KEY-TH_CPG1511F01S0X_1")
      (fields (field (name "Manufacturer") "Kailh(凯华)"))
      (libsource (lib "easyedapro") (part "CPG151101S21 RF v1.0"))
    )
    (comp (ref "SW223")
      (value "CPG151101S21")
      (footprint "easyedapro:KEY-TH_CPG1511F01S0X_1")
      (fields (field (name "Manufacturer") "Kailh(凯华)"))
      (libsource (lib "easyedapro") (part "CPG151101S21 RF v1.0"))
    )
    (comp (ref "SW224")
      (value "CPG151101S21")
      (footprint "easyedapro:KEY-TH_CPG1511F01S0X_1")
      (fields (field (name "Manufacturer") "Kailh(凯华)"))
      (libsource (lib "easyedapro") (part "CPG151101S21 RF v1.0"))
    )
    (comp (ref "SW225")
      (value "CPG151101S21")
      (footprint "easyedapro:KEY-TH_CPG1511F01S0X_1")
      (fields (field (name "Manufacturer") "Kailh(凯华)"))
      (libsource (lib "easyedapro") (part "CPG151101S21 RF v1.0"))
    )
    (comp (ref "SW226")
      (value "CPG151101S21")
      (footprint "easyedapro:KEY-TH_CPG1511F01S0X_1")
      (fields (field (name "Manufacturer") "Kailh(凯华)"))
      (libsource (lib "easyedapro") (part "CPG151101S21 RF v1.0"))
    )
    (comp (ref "SW227")
      (value "CPG151101S21")
      (footprint "easyedapro:KEY-TH_CPG1511F01S0X_1")
      (fields (field (name "Manufacturer") "Kailh(凯华)"))
      (libsource (lib "easyedapro") (part "CPG151101S21 RF v1.0"))
    )
    (comp (ref "SW228")
      (value "CPG151101S21")
      (footprint "easyedapro:KEY-TH_CPG1511F01S0X_1")
      (fields (field (name "Manufacturer") "Kailh(凯华)"))
      (libsource (lib "easyedapro") (part "CPG151101S21 RF v1.0"))
    )
    (comp (ref "SW229")
      (value "CPG151101S21")
      (footprint "easyedapro:KEY-TH_CPG1511F01S0X_1")
      (fields (field (name "Manufacturer") "Kailh(凯华)"))
      (libsource (lib "easyedapro") (part "CPG151101S21 RF v1.0"))
    )
    (comp (ref "SW230")
      (value "CPG151101S21")
      (footprint "easyedapro:KEY-TH_CPG1511F01S0X_1")
      (fields (field (name "Manufacturer") "Kailh(凯华)"))
      (libsource (lib "easyedapro") (part "CPG151101S21 RF v1.0"))
    )
    (comp (ref "SW231")
      (value "CPG151101S21")
      (footprint "easyedapro:KEY-TH_CPG1511F01S0X_1")
      (fields (field (name "Manufacturer") "Kailh(凯华)"))
      (libsource (lib "easyedapro") (part "CPG151101S21 RF v1.0"))
    )
    (comp (ref "SW232")
      (value "CPG151101S21")
      (footprint "easyedapro:KEY-TH_CPG1511F01S0X_1")
      (fields (field (name "Manufacturer") "Kailh(凯华)"))
      (libsource (lib "easyedapro") (part "CPG151101S21 RF v1.0"))
    )
    (comp (ref "SW233")
      (value "CPG151101S21")
      (footprint "easyedapro:KEY-TH_CPG1511F01S0X_1")
      (fields (field (name "Manufacturer") "Kailh(凯华)"))
      (libsource (lib "easyedapro") (part "CPG151101S21 RF v1.0"))
    )
    (comp (ref "SW234")
      (value "CPG151101S21")
      (footprint "easyedapro:KEY-TH_CPG1511F01S0X_1")
      (fields (field (name "Manufacturer") "Kailh(凯华)"))
      (libsource (lib "easyedapro") (part "CPG151101S21 RF v1.0"))
    )
    (comp (ref "SW235")
      (value "CPG151101S21")
      (footprint "easyedapro:KEY-TH_CPG1511F01S0X_1")
      (fields (field (name "Manufacturer") "Kailh(凯华)"))
      (libsource (lib "easyedapro") (part "CPG151101S21 RF v1.0"))
    )
    (comp (ref "SW236")
      (value "CPG151101S21")
      (footprint "easyedapro:KEY-TH_CPG1511F01S0X_1")
      (fields (field (name "Manufacturer") "Kailh(凯华)"))
      (libsource (lib "easyedapro") (part "CPG151101S21 RF v1.0"))
    )
    (comp (ref "SW237")
      (value "CPG151101S21")
      (footprint "easyedapro:KEY-TH_CPG1511F01S0X_1")
      (fields (field (name "Manufacturer") "Kailh(凯华)"))
      (libsource (lib "easyedapro") (part "CPG151101S21 RF v1.0"))
    )
    (comp (ref "SW238")
      (value "CPG151101S21")
      (footprint "easyedapro:KEY-TH_CPG1511F01S0X_1")
      (fields (field (name "Manufacturer") "Kailh(凯华)"))
      (libsource (lib "easyedapro") (part "CPG151101S21 RF v1.0"))
    )
    (comp (ref "SW239")
      (value "CPG151101S21")
      (footprint "easyedapro:KEY-TH_CPG1511F01S0X_1")
      (fields (field (name "Manufacturer") "Kailh(凯华)"))
      (libsource (lib "easyedapro") (part "CPG151101S21 RF v1.0"))
    )
    (comp (ref "SW240")
      (value "CPG151101S21")
      (footprint "easyedapro:KEY-TH_CPG1511F01S0X_1")
      (fields (field (name "Manufacturer") "Kailh(凯华)"))
      (libsource (lib "easyedapro") (part "CPG151101S21 RF v1.0"))
    )
    (comp (ref "SW241")
      (value "CPG151101S21")
      (footprint "easyedapro:KEY-TH_CPG1511F01S0X_1")
      (fields (field (name "Manufacturer") "Kailh(凯华)"))
      (libsource (lib "easyedapro") (part "CPG151101S21 RF v1.0"))
    )
    (comp (ref "SW242")
      (value "CPG151101S21")
      (footprint "easyedapro:KEY-TH_CPG1511F01S0X_1")
      (fields (field (name "Manufacturer") "Kailh(凯华)"))
      (libsource (lib "easyedapro") (part "CPG151101S21 RF v1.0"))
    )
    (comp (ref "SW243")
      (value "CPG151101S21")
      (footprint "easyedapro:KEY-TH_CPG1511F01S0X_1")
      (fields (field (name "Manufacturer") "Kailh(凯华)"))
      (libsource (lib "easyedapro") (part "CPG151101S21 RF v1.0"))
    )
    (comp (ref "SW244")
      (value "CPG151101S21")
      (footprint "easyedapro:KEY-TH_CPG1511F01S0X_1")
      (fields (field (name "Manufacturer") "Kailh(凯华)"))
      (libsource (lib "easyedapro") (part "CPG151101S21 RF v1.0"))
    )
    (comp (ref "SW245")
      (value "CPG151101S21")
      (footprint "easyedapro:KEY-TH_CPG1511F01S0X_1")
      (fields (field (name "Manufacturer") "Kailh(凯华)"))
      (libsource (lib "easyedapro") (part "CPG151101S21 RF v1.0"))
    )
    (comp (ref "SW246")
      (value "CPG151101S21")
      (footprint "easyedapro:KEY-TH_CPG1511F01S0X_1")
      (fields (field (name "Manufacturer") "Kailh(凯华)"))
      (libsource (lib "easyedapro") (part "CPG151101S21 RF v1.0"))
    )
    (comp (ref "SW247")
      (value "CPG151101S21")
      (footprint "easyedapro:KEY-TH_CPG1511F01S0X_1")
      (fields (field (name "Manufacturer") "Kailh(凯华)"))
      (libsource (lib "easyedapro") (part "CPG151101S21 RF v1.0"))
    )
    (comp (ref "SW248")
      (value "CPG151101S21")
      (footprint "easyedapro:KEY-TH_CPG1511F01S0X_1")
      (fields (field (name "Manufacturer") "Kailh(凯华)"))
      (libsource (lib "easyedapro") (part "CPG151101S21 RF v1.0"))
    )
    (comp (ref "SW249")
      (value "CPG151101S21")
      (footprint "easyedapro:KEY-TH_CPG1511F01S0X_1")
      (fields (field (name "Manufacturer") "Kailh(凯华)"))
      (libsource (lib "easyedapro") (part "CPG151101S21 RF v1.0"))
    )
    (comp (ref "SW250")
      (value "CPG151101S21")
      (footprint "easyedapro:KEY-TH_CPG1511F01S0X_1")
      (fields (field (name "Manufacturer") "Kailh(凯华)"))
      (libsource (lib "easyedapro") (part "CPG151101S21 RF v1.0"))
    )
    (comp (ref "SW251")
      (value "CPG151101S21")
      (footprint "easyedapro:KEY-TH_CPG1511F01S0X_1")
      (fields (field (name "Manufacturer") "Kailh(凯华)"))
      (libsource (lib "easyedapro") (part "CPG151101S21 RF v1.0"))
    )
    (comp (ref "SW252")
      (value "CPG151101S21")
      (footprint "easyedapro:KEY-TH_CPG1511F01S0X_1")
      (fields (field (name "Manufacturer") "Kailh(凯华)"))
      (libsource (lib "easyedapro") (part "CPG151101S21 RF v1.0"))
    )
    (comp (ref "SW253")
      (value "CPG151101S21")
      (footprint "easyedapro:KEY-TH_CPG1511F01S0X_1")
      (fields (field (name "Manufacturer") "Kailh(凯华)"))
      (libsource (lib "easyedapro") (part "CPG151101S21 RF v1.0"))
    )
    (comp (ref "SW254")
      (value "CPG151101S21")
      (footprint "easyedapro:KEY-TH_CPG1511F01S0X_1")
      (fields (field (name "Manufacturer") "Kailh(凯华)"))
      (libsource (lib "easyedapro") (part "CPG151101S21 RF v1.0"))
    )
    (comp (ref "SW255")
      (value "CPG151101S21")
      (footprint "easyedapro:KEY-TH_CPG1511F01S0X_1")
      (fields (field (name "Manufacturer") "Kailh(凯华)"))
      (libsource (lib "easyedapro") (part "CPG151101S21 RF v1.0"))
    )
    (comp (ref "SW256")
      (value "CPG151101S21")
      (footprint "easyedapro:KEY-TH_CPG1511F01S0X_1")
      (fields (field (name "Manufacturer") "Kailh(凯华)"))
      (libsource (lib "easyedapro") (part "CPG151101S21 RF v1.0"))
    )
    (comp (ref "SW257")
      (value "CPG151101S21")
      (footprint "easyedapro:KEY-TH_CPG1511F01S0X_1")
      (fields (field (name "Manufacturer") "Kailh(凯华)"))
      (libsource (lib "easyedapro") (part "CPG151101S21 RF v1.0"))
    )
    (comp (ref "SW258")
      (value "CPG151101S21")
      (footprint "easyedapro:KEY-TH_CPG1511F01S0X_1")
      (fields (field (name "Manufacturer") "Kailh(凯华)"))
      (libsource (lib "easyedapro") (part "CPG151101S21 RF v1.0"))
    )
    (comp (ref "SW259")
      (value "CPG151101S21")
      (footprint "easyedapro:KEY-TH_CPG1511F01S0X_1")
      (fields (field (name "Manufacturer") "Kailh(凯华)"))
      (libsource (lib "easyedapro") (part "CPG151101S21 RF v1.0"))
    )
    (comp (ref "SW260")
      (value "CPG151101S21")
      (footprint "easyedapro:KEY-TH_CPG1511F01S0X_1")
      (fields (field (name "Manufacturer") "Kailh(凯华)"))
      (libsource (lib "easyedapro") (part "CPG151101S21 RF v1.0"))
    )
    (comp (ref "SW261")
      (value "CPG151101S21")
      (footprint "easyedapro:KEY-TH_CPG1511F01S0X_1")
      (fields (field (name "Manufacturer") "Kailh(凯华)"))
      (libsource (lib "easyedapro") (part "CPG151101S21 RF v1.0"))
    )
    (comp (ref "SW262")
      (value "CPG151101S21")
      (footprint "easyedapro:KEY-TH_CPG1511F01S0X_1")
      (fields (field (name "Manufacturer") "Kailh(凯华)"))
      (libsource (lib "easyedapro") (part "CPG151101S21 RF v1.0"))
    )
    (comp (ref "SW263")
      (value "CPG151101S21")
      (footprint "easyedapro:KEY-TH_CPG1511F01S0X_1")
      (fields (field (name "Manufacturer") "Kailh(凯华)"))
      (libsource (lib "easyedapro") (part "CPG151101S21 RF v1.0"))
    )
    (comp (ref "SW264")
      (value "CPG151101S21")
      (footprint "easyedapro:KEY-TH_CPG1511F01S0X_1")
      (fields (field (name "Manufacturer") "Kailh(凯华)"))
      (libsource (lib "easyedapro") (part "CPG151101S21 RF v1.0"))
    )
    (comp (ref "SW265")
      (value "CPG151101S21")
      (footprint "easyedapro:KEY-TH_CPG1511F01S0X_1")
      (fields (field (name "Manufacturer") "Kailh(凯华)"))
      (libsource (lib "easyedapro") (part "CPG151101S21 RF v1.0"))
    )
    (comp (ref "SW266")
      (value "CPG151101S21")
      (footprint "easyedapro:KEY-TH_CPG1511F01S0X_1")
      (fields (field (name "Manufacturer") "Kailh(凯华)"))
      (libsource (lib "easyedapro") (part "CPG151101S21 RF v1.0"))
    )
    (comp (ref "SW267")
      (value "CPG151101S21")
      (footprint "easyedapro:KEY-TH_CPG1511F01S0X_1")
      (fields (field (name "Manufacturer") "Kailh(凯华)"))
      (libsource (lib "easyedapro") (part "CPG151101S21 RF v1.0"))
    )
    (comp (ref "SW268")
      (value "CPG151101S21")
      (footprint "easyedapro:KEY-TH_CPG1511F01S0X_1")
      (fields (field (name "Manufacturer") "Kailh(凯华)"))
      (libsource (lib "easyedapro") (part "CPG151101S21 RF v1.0"))
    )
    (comp (ref "SW269")
      (value "CPG151101S21")
      (footprint "easyedapro:KEY-TH_CPG1511F01S0X_1")
      (fields (field (name "Manufacturer") "Kailh(凯华)"))
      (libsource (lib "easyedapro") (part "CPG151101S21 RF v1.0"))
    )
    (comp (ref "SW270")
      (value "CPG151101S21")
      (footprint "easyedapro:KEY-TH_CPG1511F01S0X_1")
      (fields (field (name "Manufacturer") "Kailh(凯华)"))
      (libsource (lib "easyedapro") (part "CPG151101S21 RF v1.0"))
    )
    (comp (ref "SW271")
      (value "CPG151101S21")
      (footprint "easyedapro:KEY-TH_CPG1511F01S0X_1")
      (fields (field (name "Manufacturer") "Kailh(凯华)"))
      (libsource (lib "easyedapro") (part "CPG151101S21 RF v1.0"))
    )
    (comp (ref "SW272")
      (value "CPG151101S21")
      (footprint "easyedapro:KEY-TH_CPG1511F01S0X_1")
      (fields (field (name "Manufacturer") "Kailh(凯华)"))
      (libsource (lib "easyedapro") (part "CPG151101S21 RF v1.0"))
    )
    (comp (ref "SW273")
      (value "CPG151101S21")
      (footprint "easyedapro:KEY-TH_CPG1511F01S0X_1")
      (fields (field (name "Manufacturer") "Kailh(凯华)"))
      (libsource (lib "easyedapro") (part "CPG151101S21 RF v1.0"))
    )
    (comp (ref "SW274")
      (value "CPG151101S21")
      (footprint "easyedapro:KEY-TH_CPG1511F01S0X_1")
      (fields (field (name "Manufacturer") "Kailh(凯华)"))
      (libsource (lib "easyedapro") (part "CPG151101S21 RF v1.0"))
    )
    (comp (ref "SW275")
      (value "CPG151101S21")
      (footprint "easyedapro:KEY-TH_CPG1511F01S0X_1")
      (fields (field (name "Manufacturer") "Kailh(凯华)"))
      (libsource (lib "easyedapro") (part "CPG151101S21 RF v1.0"))
    )
    (comp (ref "SW276")
      (value "CPG151101S21")
      (footprint "easyedapro:KEY-TH_CPG1511F01S0X_1")
      (fields (field (name "Manufacturer") "Kailh(凯华)"))
      (libsource (lib "easyedapro") (part "CPG151101S21 RF v1.0"))
    )
    (comp (ref "SW277")
      (value "CPG151101S21")
      (footprint "easyedapro:KEY-TH_CPG1511F01S0X_1")
      (fields (field (name "Manufacturer") "Kailh(凯华)"))
      (libsource (lib "easyedapro") (part "CPG151101S21 RF v1.0"))
    )
    (comp (ref "SW278")
      (value "CPG151101S21")
      (footprint "easyedapro:KEY-TH_CPG1511F01S0X_1")
      (fields (field (name "Manufacturer") "Kailh(凯华)"))
      (libsource (lib "easyedapro") (part "CPG151101S21 RF v1.0"))
    )
  )
  (nets
    (net (code "1") (name "+1V1") (class "Default")
      (node (ref "C107") (pin "2") (pinfunction "2_2") (pintype "unspecified"))
      (node (ref "C108") (pin "2") (pinfunction "2_2") (pintype "unspecified"))
      (node (ref "C109") (pin "2") (pinfunction "2_2") (pintype "unspecified"))
      (node (ref "U101") (pin "23") (pinfunction "DVDD_23") (pintype "bidirectional"))
      (node (ref "U101") (pin "45") (pinfunction "VREG_VOUT_45") (pintype "bidirectional"))
      (node (ref "U101") (pin "50") (pinfunction "DVDD_50") (pintype "bidirectional"))
    )
    (net (code "2") (name "+3V3") (class "Default")
      (node (ref "C101") (pin "2") (pinfunction "2_2") (pintype "unspecified"))
      (node (ref "C102") (pin "2") (pinfunction "2_2") (pintype "unspecified"))
      (node (ref "C103") (pin "2") (pinfunction "2_2") (pintype "unspecified"))
      (node (ref "C104") (pin "2") (pinfunction "2_2") (pintype "unspecified"))
      (node (ref "C106") (pin "2") (pinfunction "2_2") (pintype "unspecified"))
      (node (ref "C112") (pin "2") (pinfunction "2_2") (pintype "unspecified"))
      (node (ref "C113") (pin "2") (pinfunction "2_2") (pintype "unspecified"))
      (node (ref "C114") (pin "2") (pinfunction "2_2") (pintype "unspecified"))
      (node (ref "C115") (pin "2") (pinfunction "2_2") (pintype "unspecified"))
      (node (ref "C116") (pin "2") (pinfunction "2_2") (pintype "unspecified"))
      (node (ref "C126") (pin "2") (pinfunction "2_2") (pintype "unspecified"))
      (node (ref "C201") (pin "2") (pinfunction "2_2") (pintype "unspecified"))
      (node (ref "R101") (pin "1") (pinfunction "1_1") (pintype "input"))
      (node (ref "R104") (pin "2") (pinfunction "2_2") (pintype "input"))
      (node (ref "R122") (pin "2") (pinfunction "2_2") (pintype "input"))
      (node (ref "R123") (pin "2") (pinfunction "2_2") (pintype "input"))
      (node (ref "R201") (pin "2") (pinfunction "2_2") (pintype "input"))
      (node (ref "R202") (pin "2") (pinfunction "2_2") (pintype "input"))
      (node (ref "R223") (pin "2") (pinfunction "2_2") (pintype "input"))
      (node (ref "R224") (pin "2") (pinfunction "2_2") (pintype "input"))
      (node (ref "U101") (pin "1") (pinfunction "IOVDD_1") (pintype "bidirectional"))
      (node (ref "U101") (pin "10") (pinfunction "IOVDD_10") (pintype "bidirectional"))
      (node (ref "U101") (pin "22") (pinfunction "IOVDD_22") (pintype "bidirectional"))
      (node (ref "U101") (pin "33") (pinfunction "IOVDD_33") (pintype "bidirectional"))
      (node (ref "U101") (pin "42") (pinfunction "IOVDD_42") (pintype "bidirectional"))
      (node (ref "U101") (pin "44") (pinfunction "VREG_IN_44") (pintype "bidirectional"))
      (node (ref "U101") (pin "48") (pinfunction "USB_VDD_48") (pintype "bidirectional"))
      (node (ref "U101") (pin "49") (pinfunction "IOVDD_49") (pintype "bidirectional"))
      (node (ref "U102") (pin "3") (pinfunction "OUT_3") (pintype "unspecified"))
      (node (ref "U104") (pin "8") (pinfunction "VCC_8") (pintype "unspecified"))
    )
    (net (code "3") (name "+3V3_A") (class "Default")
      (node (ref "C105") (pin "2") (pinfunction "2_2") (pintype "unspecified"))
      (node (ref "R101") (pin "2") (pinfunction "2_2") (pintype "input"))
      (node (ref "U101") (pin "43") (pinfunction "ADC_AVDD_43") (pintype "bidirectional"))
    )
    (net (code "4") (name "+5V_USB") (class "Default")
      (node (ref "C111") (pin "2") (pinfunction "2_2") (pintype "unspecified"))
      (node (ref "C118") (pin "2") (pinfunction "2_2") (pintype "unspecified"))
      (node (ref "C119") (pin "2") (pinfunction "2_2") (pintype "unspecified"))
      (node (ref "D101") (pin "2") (pinfunction "2_2") (pintype "input"))
      (node (ref "D102") (pin "2") (pinfunction "2_2") (pintype "input"))
      (node (ref "J101") (pin "11") (pinfunction "VBUS_11") (pintype "unspecified"))
      (node (ref "J101") (pin "2") (pinfunction "VBUS_2") (pintype "unspecified"))
      (node (ref "U102") (pin "1") (pinfunction "IN_1") (pintype "unspecified"))
    )
    (net (code "5") (name "COL0") (class "Default")
      (node (ref "J201") (pin "1") (pinfunction "1_1") (pintype "input"))
      (node (ref "J204") (pin "1") (pinfunction "1_1") (pintype "input"))
      (node (ref "J207") (pin "1") (pinfunction "1_1") (pintype "input"))
      (node (ref "J240") (pin "1") (pinfunction "1_1") (pintype "input"))
      (node (ref "J243") (pin "1") (pinfunction "1_1") (pintype "input"))
      (node (ref "J246") (pin "1") (pinfunction "1_1") (pintype "input"))
      (node (ref "R108") (pin "2") (pinfunction "2_2") (pintype "input"))
    )
    (net (code "6") (name "COL0_R") (class "Default")
      (node (ref "R108") (pin "1") (pinfunction "1_1") (pintype "input"))
      (node (ref "U101") (pin "2") (pinfunction "GPIO0_2") (pintype "bidirectional"))
    )
    (net (code "7") (name "COL1") (class "Default")
      (node (ref "J202") (pin "1") (pinfunction "1_1") (pintype "input"))
      (node (ref "J205") (pin "1") (pinfunction "1_1") (pintype "input"))
      (node (ref "J208") (pin "1") (pinfunction "1_1") (pintype "input"))
      (node (ref "J241") (pin "1") (pinfunction "1_1") (pintype "input"))
      (node (ref "J244") (pin "1") (pinfunction "1_1") (pintype "input"))
      (node (ref "J247") (pin "1") (pinfunction "1_1") (pintype "input"))
      (node (ref "R110") (pin "2") (pinfunction "2_2") (pintype "input"))
    )
    (net (code "8") (name "COL1_R") (class "Default")
      (node (ref "R110") (pin "1") (pinfunction "1_1") (pintype "input"))
      (node (ref "U101") (pin "3") (pinfunction "GPIO1_3") (pintype "bidirectional"))
    )
    (net (code "9") (name "COL2") (class "Default")
      (node (ref "J203") (pin "1") (pinfunction "1_1") (pintype "input"))
      (node (ref "J206") (pin "1") (pinfunction "1_1") (pintype "input"))
      (node (ref "J209") (pin "1") (pinfunction "1_1") (pintype "input"))
      (node (ref "J242") (pin "1") (pinfunction "1_1") (pintype "input"))
      (node (ref "J245") (pin "1") (pinfunction "1_1") (pintype "input"))
      (node (ref "J248") (pin "1") (pinfunction "1_1") (pintype "input"))
      (node (ref "R112") (pin "2") (pinfunction "2_2") (pintype "input"))
    )
    (net (code "10") (name "COL2_R") (class "Default")
      (node (ref "R112") (pin "1") (pinfunction "1_1") (pintype "input"))
      (node (ref "U101") (pin "4") (pinfunction "GPIO2_4") (pintype "bidirectional"))
    )
    (net (code "11") (name "COL3") (class "Default")
      (node (ref "J210") (pin "1") (pinfunction "1_1") (pintype "input"))
      (node (ref "J213") (pin "1") (pinfunction "1_1") (pintype "input"))
      (node (ref "J216") (pin "1") (pinfunction "1_1") (pintype "input"))
      (node (ref "J249") (pin "1") (pinfunction "1_1") (pintype "input"))
      (node (ref "J252") (pin "1") (pinfunction "1_1") (pintype "input"))
      (node (ref "J255") (pin "1") (pinfunction "1_1") (pintype "input"))
      (node (ref "R113") (pin "2") (pinfunction "2_2") (pintype "input"))
    )
    (net (code "12") (name "COL3_R") (class "Default")
      (node (ref "R113") (pin "1") (pinfunction "1_1") (pintype "input"))
      (node (ref "U101") (pin "5") (pinfunction "GPIO3_5") (pintype "bidirectional"))
    )
    (net (code "13") (name "COL4") (class "Default")
      (node (ref "J211") (pin "1") (pinfunction "1_1") (pintype "input"))
      (node (ref "J214") (pin "1") (pinfunction "1_1") (pintype "input"))
      (node (ref "J217") (pin "1") (pinfunction "1_1") (pintype "input"))
      (node (ref "J250") (pin "1") (pinfunction "1_1") (pintype "input"))
      (node (ref "J253") (pin "1") (pinfunction "1_1") (pintype "input"))
      (node (ref "J256") (pin "1") (pinfunction "1_1") (pintype "input"))
      (node (ref "R208") (pin "2") (pinfunction "2_2") (pintype "input"))
    )
    (net (code "14") (name "COL4_R") (class "Default")
      (node (ref "R208") (pin "1") (pinfunction "1_1") (pintype "input"))
      (node (ref "U101") (pin "6") (pinfunction "GPIO4_6") (pintype "bidirectional"))
    )
    (net (code "15") (name "COL5") (class "Default")
      (node (ref "J212") (pin "1") (pinfunction "1_1") (pintype "input"))
      (node (ref "J215") (pin "1") (pinfunction "1_1") (pintype "input"))
      (node (ref "J218") (pin "1") (pinfunction "1_1") (pintype "input"))
      (node (ref "J251") (pin "1") (pinfunction "1_1") (pintype "input"))
      (node (ref "J254") (pin "1") (pinfunction "1_1") (pintype "input"))
      (node (ref "J257") (pin "1") (pinfunction "1_1") (pintype "input"))
      (node (ref "R209") (pin "2") (pinfunction "2_2") (pintype "input"))
    )
    (net (code "16") (name "COL5_R") (class "Default")
      (node (ref "R209") (pin "1") (pinfunction "1_1") (pintype "input"))
      (node (ref "U101") (pin "7") (pinfunction "GPIO5_7") (pintype "bidirectional"))
    )
    (net (code "17") (name "COL6") (class "Default")
      (node (ref "J219") (pin "1") (pinfunction "1_1") (pintype "input"))
      (node (ref "J222") (pin "1") (pinfunction "1_1") (pintype "input"))
      (node (ref "J225") (pin "1") (pinfunction "1_1") (pintype "input"))
      (node (ref "J258") (pin "1") (pinfunction "1_1") (pintype "input"))
      (node (ref "J261") (pin "1") (pinfunction "1_1") (pintype "input"))
      (node (ref "J264") (pin "1") (pinfunction "1_1") (pintype "input"))
      (node (ref "R210") (pin "2") (pinfunction "2_2") (pintype "input"))
    )
    (net (code "18") (name "COL6_R") (class "Default")
      (node (ref "R210") (pin "1") (pinfunction "1_1") (pintype "input"))
      (node (ref "U101") (pin "8") (pinfunction "GPIO6_8") (pintype "bidirectional"))
    )
    (net (code "19") (name "COL7") (class "Default")
      (node (ref "J220") (pin "1") (pinfunction "1_1") (pintype "input"))
      (node (ref "J223") (pin "1") (pinfunction "1_1") (pintype "input"))
      (node (ref "J226") (pin "1") (pinfunction "1_1") (pintype "input"))
      (node (ref "J259") (pin "1") (pinfunction "1_1") (pintype "input"))
      (node (ref "J262") (pin "1") (pinfunction "1_1") (pintype "input"))
      (node (ref "J265") (pin "1") (pinfunction "1_1") (pintype "input"))
      (node (ref "R211") (pin "2") (pinfunction "2_2") (pintype "input"))
    )
    (net (code "20") (name "COL7_R") (class "Default")
      (node (ref "R211") (pin "1") (pinfunction "1_1") (pintype "input"))
      (node (ref "U101") (pin "9") (pinfunction "GPIO7_9") (pintype "bidirectional"))
    )
    (net (code "21") (name "COL8") (class "Default")
      (node (ref "J221") (pin "1") (pinfunction "1_1") (pintype "input"))
      (node (ref "J224") (pin "1") (pinfunction "1_1") (pintype "input"))
      (node (ref "J227") (pin "1") (pinfunction "1_1") (pintype "input"))
      (node (ref "J260") (pin "1") (pinfunction "1_1") (pintype "input"))
      (node (ref "J263") (pin "1") (pinfunction "1_1") (pintype "input"))
      (node (ref "J266") (pin "1") (pinfunction "1_1") (pintype "input"))
      (node (ref "R212") (pin "2") (pinfunction "2_2") (pintype "input"))
    )
    (net (code "22") (name "COL8_R") (class "Default")
      (node (ref "R212") (pin "1") (pinfunction "1_1") (pintype "input"))
      (node (ref "U101") (pin "11") (pinfunction "GPIO8_11") (pintype "bidirectional"))
    )
    (net (code "23") (name "COL9") (class "Default")
      (node (ref "J228") (pin "1") (pinfunction "1_1") (pintype "input"))
      (node (ref "J231") (pin "1") (pinfunction "1_1") (pintype "input"))
      (node (ref "J234") (pin "1") (pinfunction "1_1") (pintype "input"))
      (node (ref "J267") (pin "1") (pinfunction "1_1") (pintype "input"))
      (node (ref "J270") (pin "1") (pinfunction "1_1") (pintype "input"))
      (node (ref "J273") (pin "1") (pinfunction "1_1") (pintype "input"))
      (node (ref "R213") (pin "2") (pinfunction "2_2") (pintype "input"))
    )
    (net (code "24") (name "COL9_R") (class "Default")
      (node (ref "R213") (pin "1") (pinfunction "1_1") (pintype "input"))
      (node (ref "U101") (pin "12") (pinfunction "GPIO9_12") (pintype "bidirectional"))
    )
    (net (code "25") (name "COL10") (class "Default")
      (node (ref "J229") (pin "1") (pinfunction "1_1") (pintype "input"))
      (node (ref "J232") (pin "1") (pinfunction "1_1") (pintype "input"))
      (node (ref "J235") (pin "1") (pinfunction "1_1") (pintype "input"))
      (node (ref "J268") (pin "1") (pinfunction "1_1") (pintype "input"))
      (node (ref "J271") (pin "1") (pinfunction "1_1") (pintype "input"))
      (node (ref "J274") (pin "1") (pinfunction "1_1") (pintype "input"))
      (node (ref "R214") (pin "2") (pinfunction "2_2") (pintype "input"))
    )
    (net (code "26") (name "COL10_R") (class "Default")
      (node (ref "R214") (pin "1") (pinfunction "1_1") (pintype "input"))
      (node (ref "U101") (pin "13") (pinfunction "GPIO10_13") (pintype "bidirectional"))
    )
    (net (code "27") (name "COL11") (class "Default")
      (node (ref "J230") (pin "1") (pinfunction "1_1") (pintype "input"))
      (node (ref "J233") (pin "1") (pinfunction "1_1") (pintype "input"))
      (node (ref "J236") (pin "1") (pinfunction "1_1") (pintype "input"))
      (node (ref "J269") (pin "1") (pinfunction "1_1") (pintype "input"))
      (node (ref "J272") (pin "1") (pinfunction "1_1") (pintype "input"))
      (node (ref "J275") (pin "1") (pinfunction "1_1") (pintype "input"))
      (node (ref "R215") (pin "2") (pinfunction "2_2") (pintype "input"))
    )
    (net (code "28") (name "COL11_R") (class "Default")
      (node (ref "R215") (pin "1") (pinfunction "1_1") (pintype "input"))
      (node (ref "U101") (pin "14") (pinfunction "GPIO11_14") (pintype "bidirectional"))
    )
    (net (code "29") (name "COL12") (class "Default")
      (node (ref "J237") (pin "1") (pinfunction "1_1") (pintype "input"))
      (node (ref "J238") (pin "1") (pinfunction "1_1") (pintype "input"))
      (node (ref "J239") (pin "1") (pinfunction "1_1") (pintype "input"))
      (node (ref "J276") (pin "1") (pinfunction "1_1") (pintype "input"))
      (node (ref "J277") (pin "1") (pinfunction "1_1") (pintype "input"))
      (node (ref "J278") (pin "1") (pinfunction "1_1") (pintype "input"))
      (node (ref "R216") (pin "2") (pinfunction "2_2") (pintype "input"))
    )
    (net (code "30") (name "COL12_R") (class "Default")
      (node (ref "R216") (pin "1") (pinfunction "1_1") (pintype "input"))
      (node (ref "U101") (pin "15") (pinfunction "GPIO12_15") (pintype "bidirectional"))
    )
    (net (code "31") (name "CON_USB_N") (class "Default")
      (node (ref "D103") (pin "2") (pinfunction "2_2") (pintype "input"))
      (node (ref "J101") (pin "5") (pinfunction "DN2_5") (pintype "unspecified"))
      (node (ref "J101") (pin "7") (pinfunction "DN1_7") (pintype "unspecified"))
      (node (ref "R109") (pin "1") (pinfunction "1_1") (pintype "input"))
    )
    (net (code "32") (name "CON_USB_P") (class "Default")
      (node (ref "D104") (pin "2") (pinfunction "2_2") (pintype "input"))
      (node (ref "J101") (pin "6") (pinfunction "DP1_6") (pintype "unspecified"))
      (node (ref "J101") (pin "8") (pinfunction "DP2_8") (pintype "unspecified"))
      (node (ref "R111") (pin "1") (pinfunction "1_1") (pintype "input"))
    )
    (net (code "33") (name "CS") (class "Default")
      (node (ref "FPC1") (pin "5") (pinfunction "5_5") (pintype "unspecified"))
      (node (ref "U101") (pin "32") (pinfunction "GPIO21_32") (pintype "bidirectional"))
    )
    (net (code "34") (name "ENC1_A") (class "Default")
      (node (ref "C203") (pin "2") (pinfunction "2_2") (pintype "input"))
      (node (ref "R205") (pin "1") (pinfunction "1_1") (pintype "input"))
      (node (ref "U101") (pin "30") (pinfunction "GPIO19_30") (pintype "bidirectional"))
    )
    (net (code "35") (name "ENC1_B") (class "Default")
      (node (ref "C204") (pin "2") (pinfunction "2_2") (pintype "input"))
      (node (ref "R207") (pin "1") (pinfunction "1_1") (pintype "input"))
      (node (ref "U101") (pin "31") (pinfunction "GPIO20_31") (pintype "bidirectional"))
    )
    (net (code "36") (name "GND") (class "Default")
      (node (ref "C101") (pin "1") (pinfunction "1_1") (pintype "unspecified"))
      (node (ref "C102") (pin "1") (pinfunction "1_1") (pintype "unspecified"))
      (node (ref "C103") (pin "1") (pinfunction "1_1") (pintype "unspecified"))
      (node (ref "C104") (pin "1") (pinfunction "1_1") (pintype "unspecified"))
      (node (ref "C105") (pin "1") (pinfunction "1_1") (pintype "unspecified"))
      (node (ref "C106") (pin "1") (pinfunction "1_1") (pintype "unspecified"))
      (node (ref "C107") (pin "1") (pinfunction "1_1") (pintype "unspecified"))
      (node (ref "C108") (pin "1") (pinfunction "1_1") (pintype "unspecified"))
      (node (ref "C109") (pin "1") (pinfunction "1_1") (pintype "unspecified"))
      (node (ref "C111") (pin "1") (pinfunction "1_1") (pintype "unspecified"))
      (node (ref "C112") (pin "1") (pinfunction "1_1") (pintype "unspecified"))
      (node (ref "C113") (pin "1") (pinfunction "1_1") (pintype "unspecified"))
      (node (ref "C114") (pin "1") (pinfunction "1_1") (pintype "unspecified"))
      (node (ref "C115") (pin "1") (pinfunction "1_1") (pintype "unspecified"))
      (node (ref "C116") (pin "1") (pinfunction "1_1") (pintype "unspecified"))
      (node (ref "C118") (pin "1") (pinfunction "1_1") (pintype "unspecified"))
      (node (ref "C119") (pin "1") (pinfunction "1_1") (pintype "unspecified"))
      (node (ref "C123") (pin "2") (pinfunction "2_2") (pintype "unspecified"))
      (node (ref "C124") (pin "2") (pinfunction "2_2") (pintype "unspecified"))
      (node (ref "C126") (pin "1") (pinfunction "1_1") (pintype "unspecified"))
      (node (ref "C127") (pin "1") (pinfunction "1_1") (pintype "unspecified"))
      (node (ref "C201") (pin "1") (pinfunction "1_1") (pintype "unspecified"))
      (node (ref "C203") (pin "1") (pinfunction "1_1") (pintype "input"))
      (node (ref "C204") (pin "1") (pinfunction "1_1") (pintype "input"))
      (node (ref "D101") (pin "1") (pinfunction "1_1") (pintype "input"))
      (node (ref "D102") (pin "1") (pinfunction "1_1") (pintype "input"))
      (node (ref "D103") (pin "1") (pinfunction "1_1") (pintype "input"))
      (node (ref "D104") (pin "1") (pinfunction "1_1") (pintype "input"))
      (node (ref "ENC201") (pin "3") (pinfunction "3_3") (pintype "input"))
      (node (ref "ENC201") (pin "4") (pinfunction "4_4") (pintype "input"))
      (node (ref "ENC201") (pin "C") (pinfunction "C_C") (pintype "input"))
      (node (ref "FPC1") (pin "10") (pinfunction "10_10") (pintype "unspecified"))
      (node (ref "FPC1") (pin "8") (pinfunction "8_8") (pintype "unspecified"))
      (node (ref "J101") (pin "1") (pinfunction "GND_1") (pintype "unspecified"))
      (node (ref "J101") (pin "12") (pinfunction "GND_12") (pintype "unspecified"))
      (node (ref "J101") (pin "13") (pinfunction "SHELL_13") (pintype "unspecified"))
      (node (ref "J101") (pin "14") (pinfunction "SHELL_14") (pintype "unspecified"))
      (node (ref "J102") (pin "2") (pinfunction "2_2") (pintype "input"))
      (node (ref "LED102") (pin "2") (pinfunction "K_2") (pintype "unspecified"))
      (node (ref "MH201") (pin "1") (pinfunction "1_1") (pintype "input"))
      (node (ref "MH202") (pin "1") (pinfunction "1_1") (pintype "input"))
      (node (ref "MH203") (pin "1") (pinfunction "1_1") (pintype "input"))
      (node (ref "MH204") (pin "1") (pinfunction "1_1") (pintype "input"))
      (node (ref "MH205") (pin "1") (pinfunction "1_1") (pintype "input"))
      (node (ref "MH206") (pin "1") (pinfunction "1_1") (pintype "input"))
      (node (ref "MH207") (pin "1") (pinfunction "1_1") (pintype "input"))
      (node (ref "MH208") (pin "1") (pinfunction "1_1") (pintype "input"))
      (node (ref "R118") (pin "1") (pinfunction "1_1") (pintype "input"))
      (node (ref "R119") (pin "1") (pinfunction "1_1") (pintype "input"))
      (node (ref "SW101") (pin "1") (pinfunction "A_1") (pintype "input"))
      (node (ref "SW101") (pin "2") (pinfunction "B_2") (pintype "input"))
      (node (ref "SW102") (pin "1") (pinfunction "A_1") (pintype "input"))
      (node (ref "SW102") (pin "2") (pinfunction "B_2") (pintype "input"))
      (node (ref "U101") (pin "19") (pinfunction "TESTEN_19") (pintype "unspecified"))
      (node (ref "U101") (pin "57") (pinfunction "GND_57") (pintype "bidirectional"))
      (node (ref "U102") (pin "2") (pinfunction "GND_2") (pintype "unspecified"))
      (node (ref "U102") (pin "4") (pinfunction "GND_4") (pintype "unspecified"))
      (node (ref "U104") (pin "4") (pinfunction "GND_4") (pintype "unspecified"))
      (node (ref "Y101") (pin "2") (pinfunction "GND_2") (pintype "input"))
      (node (ref "Y101") (pin "4") (pinfunction "GND_4") (pintype "input"))
    )
    (net (code "37") (name "Net-(D201-A)") (class "Default")
      (node (ref "D201") (pin "2") (pinfunction "A_2") (pintype "input"))
      (node (ref "J201") (pin "2") (pinfunction "2_2") (pintype "input"))
    )
    (net (code "38") (name "Net-(D202-A)") (class "Default")
      (node (ref "D202") (pin "2") (pinfunction "A_2") (pintype "input"))
      (node (ref "J202") (pin "2") (pinfunction "2_2") (pintype "input"))
    )
    (net (code "39") (name "Net-(D203-A)") (class "Default")
      (node (ref "D203") (pin "2") (pinfunction "A_2") (pintype "input"))
      (node (ref "J203") (pin "2") (pinfunction "2_2") (pintype "input"))
    )
    (net (code "40") (name "Net-(D204-A)") (class "Default")
      (node (ref "D204") (pin "2") (pinfunction "A_2") (pintype "input"))
      (node (ref "J204") (pin "2") (pinfunction "2_2") (pintype "input"))
    )
    (net (code "41") (name "Net-(D205-A)") (class "Default")
      (node (ref "D205") (pin "2") (pinfunction "A_2") (pintype "input"))
      (node (ref "J205") (pin "2") (pinfunction "2_2") (pintype "input"))
    )
    (net (code "42") (name "Net-(D206-A)") (class "Default")
      (node (ref "D206") (pin "2") (pinfunction "A_2") (pintype "input"))
      (node (ref "J206") (pin "2") (pinfunction "2_2") (pintype "input"))
    )
    (net (code "43") (name "Net-(D207-A)") (class "Default")
      (node (ref "D207") (pin "2") (pinfunction "A_2") (pintype "input"))
      (node (ref "J207") (pin "2") (pinfunction "2_2") (pintype "input"))
    )
    (net (code "44") (name "Net-(D208-A)") (class "Default")
      (node (ref "D208") (pin "2") (pinfunction "A_2") (pintype "input"))
      (node (ref "J208") (pin "2") (pinfunction "2_2") (pintype "input"))
    )
    (net (code "45") (name "Net-(D209-A)") (class "Default")
      (node (ref "D209") (pin "2") (pinfunction "A_2") (pintype "input"))
      (node (ref "J209") (pin "2") (pinfunction "2_2") (pintype "input"))
    )
    (net (code "46") (name "Net-(D213-A)") (class "Default")
      (node (ref "D213") (pin "2") (pinfunction "A_2") (pintype "input"))
      (node (ref "J210") (pin "2") (pinfunction "2_2") (pintype "input"))
    )
    (net (code "47") (name "Net-(D214-A)") (class "Default")
      (node (ref "D214") (pin "2") (pinfunction "A_2") (pintype "input"))
      (node (ref "J211") (pin "2") (pinfunction "2_2") (pintype "input"))
    )
    (net (code "48") (name "Net-(D215-A)") (class "Default")
      (node (ref "D215") (pin "2") (pinfunction "A_2") (pintype "input"))
      (node (ref "J212") (pin "2") (pinfunction "2_2") (pintype "input"))
    )
    (net (code "49") (name "Net-(D216-A)") (class "Default")
      (node (ref "D216") (pin "2") (pinfunction "A_2") (pintype "input"))
      (node (ref "J213") (pin "2") (pinfunction "2_2") (pintype "input"))
    )
    (net (code "50") (name "Net-(D217-A)") (class "Default")
      (node (ref "D217") (pin "2") (pinfunction "A_2") (pintype "input"))
      (node (ref "J214") (pin "2") (pinfunction "2_2") (pintype "input"))
    )
    (net (code "51") (name "Net-(D218-A)") (class "Default")
      (node (ref "D218") (pin "2") (pinfunction "A_2") (pintype "input"))
      (node (ref "J215") (pin "2") (pinfunction "2_2") (pintype "input"))
    )
    (net (code "52") (name "Net-(D219-A)") (class "Default")
      (node (ref "D219") (pin "2") (pinfunction "A_2") (pintype "input"))
      (node (ref "J216") (pin "2") (pinfunction "2_2") (pintype "input"))
    )
    (net (code "53") (name "Net-(D220-A)") (class "Default")
      (node (ref "D220") (pin "2") (pinfunction "A_2") (pintype "input"))
      (node (ref "J217") (pin "2") (pinfunction "2_2") (pintype "input"))
    )
    (net (code "54") (name "Net-(D221-A)") (class "Default")
      (node (ref "D221") (pin "2") (pinfunction "A_2") (pintype "input"))
      (node (ref "J218") (pin "2") (pinfunction "2_2") (pintype "input"))
    )
    (net (code "55") (name "Net-(D225-A)") (class "Default")
      (node (ref "D225") (pin "2") (pinfunction "A_2") (pintype "input"))
      (node (ref "J219") (pin "2") (pinfunction "2_2") (pintype "input"))
    )
    (net (code "56") (name "Net-(D226-A)") (class "Default")
      (node (ref "D226") (pin "2") (pinfunction "A_2") (pintype "input"))
      (node (ref "J220") (pin "2") (pinfunction "2_2") (pintype "input"))
    )
    (net (code "57") (name "Net-(D227-A)") (class "Default")
      (node (ref "D227") (pin "2") (pinfunction "A_2") (pintype "input"))
      (node (ref "J221") (pin "2") (pinfunction "2_2") (pintype "input"))
    )
    (net (code "58") (name "Net-(D228-A)") (class "Default")
      (node (ref "D228") (pin "2") (pinfunction "A_2") (pintype "input"))
      (node (ref "J222") (pin "2") (pinfunction "2_2") (pintype "input"))
    )
    (net (code "59") (name "Net-(D229-A)") (class "Default")
      (node (ref "D229") (pin "2") (pinfunction "A_2") (pintype "input"))
      (node (ref "J223") (pin "2") (pinfunction "2_2") (pintype "input"))
    )
    (net (code "60") (name "Net-(D230-A)") (class "Default")
      (node (ref "D230") (pin "2") (pinfunction "A_2") (pintype "input"))
      (node (ref "J224") (pin "2") (pinfunction "2_2") (pintype "input"))
    )
    (net (code "61") (name "Net-(D231-A)") (class "Default")
      (node (ref "D231") (pin "2") (pinfunction "A_2") (pintype "input"))
      (node (ref "J225") (pin "2") (pinfunction "2_2") (pintype "input"))
    )
    (net (code "62") (name "Net-(D232-A)") (class "Default")
      (node (ref "D232") (pin "2") (pinfunction "A_2") (pintype "input"))
      (node (ref "J226") (pin "2") (pinfunction "2_2") (pintype "input"))
    )
    (net (code "63") (name "Net-(D233-A)") (class "Default")
      (node (ref "D233") (pin "2") (pinfunction "A_2") (pintype "input"))
      (node (ref "J227") (pin "2") (pinfunction "2_2") (pintype "input"))
    )
    (net (code "64") (name "Net-(D237-A)") (class "Default")
      (node (ref "D237") (pin "2") (pinfunction "A_2") (pintype "input"))
      (node (ref "J228") (pin "2") (pinfunction "2_2") (pintype "input"))
    )
    (net (code "65") (name "Net-(D238-A)") (class "Default")
      (node (ref "D238") (pin "2") (pinfunction "A_2") (pintype "input"))
      (node (ref "J229") (pin "2") (pinfunction "2_2") (pintype "input"))
    )
    (net (code "66") (name "Net-(D239-A)") (class "Default")
      (node (ref "D239") (pin "2") (pinfunction "A_2") (pintype "input"))
      (node (ref "J230") (pin "2") (pinfunction "2_2") (pintype "input"))
    )
    (net (code "67") (name "Net-(D240-A)") (class "Default")
      (node (ref "D240") (pin "2") (pinfunction "A_2") (pintype "input"))
      (node (ref "J231") (pin "2") (pinfunction "2_2") (pintype "input"))
    )
    (net (code "68") (name "Net-(D241-A)") (class "Default")
      (node (ref "D241") (pin "2") (pinfunction "A_2") (pintype "input"))
      (node (ref "J232") (pin "2") (pinfunction "2_2") (pintype "input"))
    )
    (net (code "69") (name "Net-(D242-A)") (class "Default")
      (node (ref "D242") (pin "2") (pinfunction "A_2") (pintype "input"))
      (node (ref "J233") (pin "2") (pinfunction "2_2") (pintype "input"))
    )
    (net (code "70") (name "Net-(D243-A)") (class "Default")
      (node (ref "D243") (pin "2") (pinfunction "A_2") (pintype "input"))
      (node (ref "J234") (pin "2") (pinfunction "2_2") (pintype "input"))
    )
    (net (code "71") (name "Net-(D244-A)") (class "Default")
      (node (ref "D244") (pin "2") (pinfunction "A_2") (pintype "input"))
      (node (ref "J235") (pin "2") (pinfunction "2_2") (pintype "input"))
    )
    (net (code "72") (name "Net-(D245-A)") (class "Default")
      (node (ref "D245") (pin "2") (pinfunction "A_2") (pintype "input"))
      (node (ref "J236") (pin "2") (pinfunction "2_2") (pintype "input"))
    )
    (net (code "73") (name "Net-(D249-A)") (class "Default")
      (node (ref "D249") (pin "2") (pinfunction "A_2") (pintype "input"))
      (node (ref "J237") (pin "2") (pinfunction "2_2") (pintype "input"))
    )
    (net (code "74") (name "Net-(D250-A)") (class "Default")
      (node (ref "D250") (pin "2") (pinfunction "A_2") (pintype "input"))
      (node (ref "J238") (pin "2") (pinfunction "2_2") (pintype "input"))
    )
    (net (code "75") (name "Net-(D251-A)") (class "Default")
      (node (ref "D251") (pin "2") (pinfunction "A_2") (pintype "input"))
      (node (ref "J239") (pin "2") (pinfunction "2_2") (pintype "input"))
    )
    (net (code "76") (name "Net-(D252-A)") (class "Default")
      (node (ref "D252") (pin "2") (pinfunction "A_2") (pintype "input"))
      (node (ref "J240") (pin "2") (pinfunction "2_2") (pintype "input"))
    )
    (net (code "77") (name "Net-(D253-A)") (class "Default")
      (node (ref "D253") (pin "2") (pinfunction "A_2") (pintype "input"))
      (node (ref "J241") (pin "2") (pinfunction "2_2") (pintype "input"))
    )
    (net (code "78") (name "Net-(D254-A)") (class "Default")
      (node (ref "D254") (pin "2") (pinfunction "A_2") (pintype "input"))
      (node (ref "J242") (pin "2") (pinfunction "2_2") (pintype "input"))
    )
    (net (code "79") (name "Net-(D255-A)") (class "Default")
      (node (ref "D255") (pin "2") (pinfunction "A_2") (pintype "input"))
      (node (ref "J243") (pin "2") (pinfunction "2_2") (pintype "input"))
    )
    (net (code "80") (name "Net-(D256-A)") (class "Default")
      (node (ref "D256") (pin "2") (pinfunction "A_2") (pintype "input"))
      (node (ref "J244") (pin "2") (pinfunction "2_2") (pintype "input"))
    )
    (net (code "81") (name "Net-(D257-A)") (class "Default")
      (node (ref "D257") (pin "2") (pinfunction "A_2") (pintype "input"))
      (node (ref "J245") (pin "2") (pinfunction "2_2") (pintype "input"))
    )
    (net (code "82") (name "Net-(D258-A)") (class "Default")
      (node (ref "D258") (pin "2") (pinfunction "A_2") (pintype "input"))
      (node (ref "J246") (pin "2") (pinfunction "2_2") (pintype "input"))
    )
    (net (code "83") (name "Net-(D259-A)") (class "Default")
      (node (ref "D259") (pin "2") (pinfunction "A_2") (pintype "input"))
      (node (ref "J247") (pin "2") (pinfunction "2_2") (pintype "input"))
    )
    (net (code "84") (name "Net-(D260-A)") (class "Default")
      (node (ref "D260") (pin "2") (pinfunction "A_2") (pintype "input"))
      (node (ref "J248") (pin "2") (pinfunction "2_2") (pintype "input"))
    )
    (net (code "85") (name "Net-(D261-A)") (class "Default")
      (node (ref "D261") (pin "2") (pinfunction "A_2") (pintype "input"))
      (node (ref "J249") (pin "2") (pinfunction "2_2") (pintype "input"))
    )
    (net (code "86") (name "Net-(D262-A)") (class "Default")
      (node (ref "D262") (pin "2") (pinfunction "A_2") (pintype "input"))
      (node (ref "J250") (pin "2") (pinfunction "2_2") (pintype "input"))
    )
    (net (code "87") (name "Net-(D263-A)") (class "Default")
      (node (ref "D263") (pin "2") (pinfunction "A_2") (pintype "input"))
      (node (ref "J251") (pin "2") (pinfunction "2_2") (pintype "input"))
    )
    (net (code "88") (name "Net-(D264-A)") (class "Default")
      (node (ref "D264") (pin "2") (pinfunction "A_2") (pintype "input"))
      (node (ref "J252") (pin "2") (pinfunction "2_2") (pintype "input"))
    )
    (net (code "89") (name "Net-(D265-A)") (class "Default")
      (node (ref "D265") (pin "2") (pinfunction "A_2") (pintype "input"))
      (node (ref "J253") (pin "2") (pinfunction "2_2") (pintype "input"))
    )
    (net (code "90") (name "Net-(D266-A)") (class "Default")
      (node (ref "D266") (pin "2") (pinfunction "A_2") (pintype "input"))
      (node (ref "J254") (pin "2") (pinfunction "2_2") (pintype "input"))
    )
    (net (code "91") (name "Net-(D267-A)") (class "Default")
      (node (ref "D267") (pin "2") (pinfunction "A_2") (pintype "input"))
      (node (ref "J255") (pin "2") (pinfunction "2_2") (pintype "input"))
    )
    (net (code "92") (name "Net-(D268-A)") (class "Default")
      (node (ref "D268") (pin "2") (pinfunction "A_2") (pintype "input"))
      (node (ref "J256") (pin "2") (pinfunction "2_2") (pintype "input"))
    )
    (net (code "93") (name "Net-(D269-A)") (class "Default")
      (node (ref "D269") (pin "2") (pinfunction "A_2") (pintype "input"))
      (node (ref "J257") (pin "2") (pinfunction "2_2") (pintype "input"))
    )
    (net (code "94") (name "Net-(D270-A)") (class "Default")
      (node (ref "D270") (pin "2") (pinfunction "A_2") (pintype "input"))
      (node (ref "J258") (pin "2") (pinfunction "2_2") (pintype "input"))
    )
    (net (code "95") (name "Net-(D271-A)") (class "Default")
      (node (ref "D271") (pin "2") (pinfunction "A_2") (pintype "input"))
      (node (ref "J259") (pin "2") (pinfunction "2_2") (pintype "input"))
    )
    (net (code "96") (name "Net-(D272-A)") (class "Default")
      (node (ref "D272") (pin "2") (pinfunction "A_2") (pintype "input"))
      (node (ref "J260") (pin "2") (pinfunction "2_2") (pintype "input"))
    )
    (net (code "97") (name "Net-(D273-A)") (class "Default")
      (node (ref "D273") (pin "2") (pinfunction "A_2") (pintype "input"))
      (node (ref "J261") (pin "2") (pinfunction "2_2") (pintype "input"))
    )
    (net (code "98") (name "Net-(D274-A)") (class "Default")
      (node (ref "D274") (pin "2") (pinfunction "A_2") (pintype "input"))
      (node (ref "J262") (pin "2") (pinfunction "2_2") (pintype "input"))
    )
    (net (code "99") (name "Net-(D275-A)") (class "Default")
      (node (ref "D275") (pin "2") (pinfunction "A_2") (pintype "input"))
      (node (ref "J263") (pin "2") (pinfunction "2_2") (pintype "input"))
    )
    (net (code "100") (name "Net-(D276-A)") (class "Default")
      (node (ref "D276") (pin "2") (pinfunction "A_2") (pintype "input"))
      (node (ref "J264") (pin "2") (pinfunction "2_2") (pintype "input"))
    )
    (net (code "101") (name "Net-(D277-A)") (class "Default")
      (node (ref "D277") (pin "2") (pinfunction "A_2") (pintype "input"))
      (node (ref "J265") (pin "2") (pinfunction "2_2") (pintype "input"))
    )
    (net (code "102") (name "Net-(D278-A)") (class "Default")
      (node (ref "D278") (pin "2") (pinfunction "A_2") (pintype "input"))
      (node (ref "J266") (pin "2") (pinfunction "2_2") (pintype "input"))
    )
    (net (code "103") (name "Net-(D279-A)") (class "Default")
      (node (ref "D279") (pin "2") (pinfunction "A_2") (pintype "input"))
      (node (ref "J267") (pin "2") (pinfunction "2_2") (pintype "input"))
    )
    (net (code "104") (name "Net-(D280-A)") (class "Default")
      (node (ref "D280") (pin "2") (pinfunction "A_2") (pintype "input"))
      (node (ref "J268") (pin "2") (pinfunction "2_2") (pintype "input"))
    )
    (net (code "105") (name "Net-(D281-A)") (class "Default")
      (node (ref "D281") (pin "2") (pinfunction "A_2") (pintype "input"))
      (node (ref "J269") (pin "2") (pinfunction "2_2") (pintype "input"))
    )
    (net (code "106") (name "Net-(D282-A)") (class "Default")
      (node (ref "D282") (pin "2") (pinfunction "A_2") (pintype "input"))
      (node (ref "J270") (pin "2") (pinfunction "2_2") (pintype "input"))
    )
    (net (code "107") (name "Net-(D283-A)") (class "Default")
      (node (ref "D283") (pin "2") (pinfunction "A_2") (pintype "input"))
      (node (ref "J271") (pin "2") (pinfunction "2_2") (pintype "input"))
    )
    (net (code "108") (name "Net-(D284-A)") (class "Default")
      (node (ref "D284") (pin "2") (pinfunction "A_2") (pintype "input"))
      (node (ref "J272") (pin "2") (pinfunction "2_2") (pintype "input"))
    )
    (net (code "109") (name "Net-(D285-A)") (class "Default")
      (node (ref "D285") (pin "2") (pinfunction "A_2") (pintype "input"))
      (node (ref "J273") (pin "2") (pinfunction "2_2") (pintype "input"))
    )
    (net (code "110") (name "Net-(D286-A)") (class "Default")
      (node (ref "D286") (pin "2") (pinfunction "A_2") (pintype "input"))
      (node (ref "J274") (pin "2") (pinfunction "2_2") (pintype "input"))
    )
    (net (code "111") (name "Net-(D287-A)") (class "Default")
      (node (ref "D287") (pin "2") (pinfunction "A_2") (pintype "input"))
      (node (ref "J275") (pin "2") (pinfunction "2_2") (pintype "input"))
    )
    (net (code "112") (name "Net-(D288-A)") (class "Default")
      (node (ref "D288") (pin "2") (pinfunction "A_2") (pintype "input"))
      (node (ref "J276") (pin "2") (pinfunction "2_2") (pintype "input"))
    )
    (net (code "113") (name "Net-(D289-A)") (class "Default")
      (node (ref "D289") (pin "2") (pinfunction "A_2") (pintype "input"))
      (node (ref "J277") (pin "2") (pinfunction "2_2") (pintype "input"))
    )
    (net (code "114") (name "Net-(D290-A)") (class "Default")
      (node (ref "D290") (pin "2") (pinfunction "A_2") (pintype "input"))
      (node (ref "J278") (pin "2") (pinfunction "2_2") (pintype "input"))
    )
    (net (code "115") (name "Net-(ENC201-PadA)") (class "Default")
      (node (ref "ENC201") (pin "A") (pinfunction "A_A") (pintype "input"))
      (node (ref "R201") (pin "1") (pinfunction "1_1") (pintype "input"))
      (node (ref "R205") (pin "2") (pinfunction "2_2") (pintype "input"))
    )
    (net (code "116") (name "Net-(ENC201-PadB)") (class "Default")
      (node (ref "ENC201") (pin "B") (pinfunction "B_B") (pintype "input"))
      (node (ref "R202") (pin "1") (pinfunction "1_1") (pintype "input"))
      (node (ref "R207") (pin "2") (pinfunction "2_2") (pintype "input"))
    )
    (net (code "117") (name "Net-(FPC1-Pad7)") (class "Default")
      (node (ref "FPC1") (pin "7") (pinfunction "7_7") (pintype "unspecified"))
      (node (ref "R223") (pin "1") (pinfunction "1_1") (pintype "input"))
    )
    (net (code "118") (name "Net-(FPC1-Pad9)") (class "Default")
      (node (ref "FPC1") (pin "9") (pinfunction "9_9") (pintype "unspecified"))
      (node (ref "R224") (pin "1") (pinfunction "1_1") (pintype "input"))
    )
    (net (code "119") (name "Net-(J101-CC1)") (class "Default")
      (node (ref "J101") (pin "4") (pinfunction "CC1_4") (pintype "unspecified"))
      (node (ref "R119") (pin "2") (pinfunction "2_2") (pintype "input"))
    )
    (net (code "120") (name "Net-(J101-CC2)") (class "Default")
      (node (ref "J101") (pin "10") (pinfunction "CC2_10") (pintype "unspecified"))
      (node (ref "R118") (pin "2") (pinfunction "2_2") (pintype "input"))
    )
    (net (code "121") (name "Net-(LED102-A)") (class "Default")
      (node (ref "LED102") (pin "1") (pinfunction "A_1") (pintype "unspecified"))
      (node (ref "R104") (pin "1") (pinfunction "1_1") (pintype "input"))
    )
    (net (code "122") (name "Net-(SW101-C)") (class "Default")
      (node (ref "R122") (pin "1") (pinfunction "1_1") (pintype "input"))
      (node (ref "R124") (pin "1") (pinfunction "1_1") (pintype "input"))
      (node (ref "SW101") (pin "3") (pinfunction "C_3") (pintype "input"))
      (node (ref "SW101") (pin "4") (pinfunction "D_4") (pintype "input"))
    )
    (net (code "123") (name "Net-(SW102-C)") (class "Default")
      (node (ref "R123") (pin "1") (pinfunction "1_1") (pintype "input"))
      (node (ref "R125") (pin "1") (pinfunction "1_1") (pintype "input"))
      (node (ref "SW102") (pin "3") (pinfunction "C_3") (pintype "input"))
      (node (ref "SW102") (pin "4") (pinfunction "D_4") (pintype "input"))
    )
    (net (code "124") (name "QSPI_SCLK") (class "Default")
      (node (ref "U101") (pin "52") (pinfunction "QSPI_SCLK_52") (pintype "output"))
      (node (ref "U104") (pin "6") (pinfunction "CLK_6") (pintype "unspecified"))
    )
    (net (code "125") (name "QSPI_SD0") (class "Default")
      (node (ref "U101") (pin "53") (pinfunction "QSPI_SD0_53") (pintype "bidirectional"))
      (node (ref "U104") (pin "5") (pinfunction "DI_5") (pintype "unspecified"))
    )
    (net (code "126") (name "QSPI_SD1") (class "Default")
      (node (ref "U101") (pin "55") (pinfunction "QSPI_SD1_55") (pintype "bidirectional"))
      (node (ref "U104") (pin "2") (pinfunction "DO_2") (pintype "unspecified"))
    )
    (net (code "127") (name "QSPI_SD2") (class "Default")
      (node (ref "U101") (pin "54") (pinfunction "QSPI_SD2_54") (pintype "bidirectional"))
      (node (ref "U104") (pin "3") (pinfunction "IO2_3") (pintype "unspecified"))
    )
    (net (code "128") (name "QSPI_SD3") (class "Default")
      (node (ref "U101") (pin "51") (pinfunction "QSPI_SD3_51") (pintype "bidirectional"))
      (node (ref "U104") (pin "7") (pinfunction "IO3_7") (pintype "unspecified"))
    )
    (net (code "129") (name "QSPI_SS") (class "Default")
      (node (ref "R124") (pin "2") (pinfunction "2_2") (pintype "input"))
      (node (ref "U101") (pin "56") (pinfunction "QSPI_SS_56") (pintype "bidirectional"))
      (node (ref "U104") (pin "1") (pinfunction "CS#_1") (pintype "unspecified"))
    )
    (net (code "130") (name "RESET_N") (class "Default")
      (node (ref "C127") (pin "2") (pinfunction "2_2") (pintype "unspecified"))
      (node (ref "R125") (pin "2") (pinfunction "2_2") (pintype "input"))
      (node (ref "U101") (pin "26") (pinfunction "RUN_26") (pintype "input"))
    )
    (net (code "131") (name "ROW0") (class "Default")
      (node (ref "D201") (pin "1") (pinfunction "K_1") (pintype "input"))
      (node (ref "D202") (pin "1") (pinfunction "K_1") (pintype "input"))
      (node (ref "D203") (pin "1") (pinfunction "K_1") (pintype "input"))
      (node (ref "D213") (pin "1") (pinfunction "K_1") (pintype "input"))
      (node (ref "D214") (pin "1") (pinfunction "K_1") (pintype "input"))
      (node (ref "D215") (pin "1") (pinfunction "K_1") (pintype "input"))
      (node (ref "D225") (pin "1") (pinfunction "K_1") (pintype "input"))
      (node (ref "D226") (pin "1") (pinfunction "K_1") (pintype "input"))
      (node (ref "D227") (pin "1") (pinfunction "K_1") (pintype "input"))
      (node (ref "D237") (pin "1") (pinfunction "K_1") (pintype "input"))
      (node (ref "D238") (pin "1") (pinfunction "K_1") (pintype "input"))
      (node (ref "D239") (pin "1") (pinfunction "K_1") (pintype "input"))
      (node (ref "D249") (pin "1") (pinfunction "K_1") (pintype "input"))
      (node (ref "R217") (pin "2") (pinfunction "2_2") (pintype "input"))
    )
    (net (code "132") (name "ROW0_R") (class "Default")
      (node (ref "R217") (pin "1") (pinfunction "1_1") (pintype "input"))
      (node (ref "U101") (pin "16") (pinfunction "GPIO13_16") (pintype "bidirectional"))
    )
    (net (code "133") (name "ROW1") (class "Default")
      (node (ref "D204") (pin "1") (pinfunction "K_1") (pintype "input"))
      (node (ref "D205") (pin "1") (pinfunction "K_1") (pintype "input"))
      (node (ref "D206") (pin "1") (pinfunction "K_1") (pintype "input"))
      (node (ref "D216") (pin "1") (pinfunction "K_1") (pintype "input"))
      (node (ref "D217") (pin "1") (pinfunction "K_1") (pintype "input"))
      (node (ref "D218") (pin "1") (pinfunction "K_1") (pintype "input"))
      (node (ref "D228") (pin "1") (pinfunction "K_1") (pintype "input"))
      (node (ref "D229") (pin "1") (pinfunction "K_1") (pintype "input"))
      (node (ref "D230") (pin "1") (pinfunction "K_1") (pintype "input"))
      (node (ref "D240") (pin "1") (pinfunction "K_1") (pintype "input"))
      (node (ref "D241") (pin "1") (pinfunction "K_1") (pintype "input"))
      (node (ref "D242") (pin "1") (pinfunction "K_1") (pintype "input"))
      (node (ref "D250") (pin "1") (pinfunction "K_1") (pintype "input"))
      (node (ref "R218") (pin "2") (pinfunction "2_2") (pintype "input"))
    )
    (net (code "134") (name "ROW1_R") (class "Default")
      (node (ref "R218") (pin "1") (pinfunction "1_1") (pintype "input"))
      (node (ref "U101") (pin "17") (pinfunction "GPIO14_17") (pintype "bidirectional"))
    )
    (net (code "135") (name "ROW2") (class "Default")
      (node (ref "D207") (pin "1") (pinfunction "K_1") (pintype "input"))
      (node (ref "D208") (pin "1") (pinfunction "K_1") (pintype "input"))
      (node (ref "D209") (pin "1") (pinfunction "K_1") (pintype "input"))
      (node (ref "D219") (pin "1") (pinfunction "K_1") (pintype "input"))
      (node (ref "D220") (pin "1") (pinfunction "K_1") (pintype "input"))
      (node (ref "D221") (pin "1") (pinfunction "K_1") (pintype "input"))
      (node (ref "D231") (pin "1") (pinfunction "K_1") (pintype "input"))
      (node (ref "D232") (pin "1") (pinfunction "K_1") (pintype "input"))
      (node (ref "D233") (pin "1") (pinfunction "K_1") (pintype "input"))
      (node (ref "D243") (pin "1") (pinfunction "K_1") (pintype "input"))
      (node (ref "D244") (pin "1") (pinfunction "K_1") (pintype "input"))
      (node (ref "D245") (pin "1") (pinfunction "K_1") (pintype "input"))
      (node (ref "D251") (pin "1") (pinfunction "K_1") (pintype "input"))
      (node (ref "R219") (pin "2") (pinfunction "2_2") (pintype "input"))
    )
    (net (code "136") (name "ROW2_R") (class "Default")
      (node (ref "R219") (pin "1") (pinfunction "1_1") (pintype "input"))
      (node (ref "U101") (pin "18") (pinfunction "GPIO15_18") (pintype "bidirectional"))
    )
    (net (code "137") (name "ROW3") (class "Default")
      (node (ref "D252") (pin "1") (pinfunction "K_1") (pintype "input"))
      (node (ref "D253") (pin "1") (pinfunction "K_1") (pintype "input"))
      (node (ref "D254") (pin "1") (pinfunction "K_1") (pintype "input"))
      (node (ref "D261") (pin "1") (pinfunction "K_1") (pintype "input"))
      (node (ref "D262") (pin "1") (pinfunction "K_1") (pintype "input"))
      (node (ref "D263") (pin "1") (pinfunction "K_1") (pintype "input"))
      (node (ref "D270") (pin "1") (pinfunction "K_1") (pintype "input"))
      (node (ref "D271") (pin "1") (pinfunction "K_1") (pintype "input"))
      (node (ref "D272") (pin "1") (pinfunction "K_1") (pintype "input"))
      (node (ref "D279") (pin "1") (pinfunction "K_1") (pintype "input"))
      (node (ref "D280") (pin "1") (pinfunction "K_1") (pintype "input"))
      (node (ref "D281") (pin "1") (pinfunction "K_1") (pintype "input"))
      (node (ref "D288") (pin "1") (pinfunction "K_1") (pintype "input"))
      (node (ref "R220") (pin "2") (pinfunction "2_2") (pintype "input"))
    )
    (net (code "138") (name "ROW3_R") (class "Default")
      (node (ref "R220") (pin "1") (pinfunction "1_1") (pintype "input"))
      (node (ref "U101") (pin "27") (pinfunction "GPIO16_27") (pintype "bidirectional"))
    )
    (net (code "139") (name "ROW4") (class "Default")
      (node (ref "D255") (pin "1") (pinfunction "K_1") (pintype "input"))
      (node (ref "D256") (pin "1") (pinfunction "K_1") (pintype "input"))
      (node (ref "D257") (pin "1") (pinfunction "K_1") (pintype "input"))
      (node (ref "D264") (pin "1") (pinfunction "K_1") (pintype "input"))
      (node (ref "D265") (pin "1") (pinfunction "K_1") (pintype "input"))
      (node (ref "D266") (pin "1") (pinfunction "K_1") (pintype "input"))
      (node (ref "D273") (pin "1") (pinfunction "K_1") (pintype "input"))
      (node (ref "D274") (pin "1") (pinfunction "K_1") (pintype "input"))
      (node (ref "D275") (pin "1") (pinfunction "K_1") (pintype "input"))
      (node (ref "D282") (pin "1") (pinfunction "K_1") (pintype "input"))
      (node (ref "D283") (pin "1") (pinfunction "K_1") (pintype "input"))
      (node (ref "D284") (pin "1") (pinfunction "K_1") (pintype "input"))
      (node (ref "D289") (pin "1") (pinfunction "K_1") (pintype "input"))
      (node (ref "R221") (pin "2") (pinfunction "2_2") (pintype "input"))
    )
    (net (code "140") (name "ROW4_R") (class "Default")
      (node (ref "R221") (pin "1") (pinfunction "1_1") (pintype "input"))
      (node (ref "U101") (pin "28") (pinfunction "GPIO17_28") (pintype "bidirectional"))
    )
    (net (code "141") (name "ROW5") (class "Default")
      (node (ref "D258") (pin "1") (pinfunction "K_1") (pintype "input"))
      (node (ref "D259") (pin "1") (pinfunction "K_1") (pintype "input"))
      (node (ref "D260") (pin "1") (pinfunction "K_1") (pintype "input"))
      (node (ref "D267") (pin "1") (pinfunction "K_1") (pintype "input"))
      (node (ref "D268") (pin "1") (pinfunction "K_1") (pintype "input"))
      (node (ref "D269") (pin "1") (pinfunction "K_1") (pintype "input"))
      (node (ref "D276") (pin "1") (pinfunction "K_1") (pintype "input"))
      (node (ref "D277") (pin "1") (pinfunction "K_1") (pintype "input"))
      (node (ref "D278") (pin "1") (pinfunction "K_1") (pintype "input"))
      (node (ref "D285") (pin "1") (pinfunction "K_1") (pintype "input"))
      (node (ref "D286") (pin "1") (pinfunction "K_1") (pintype "input"))
      (node (ref "D287") (pin "1") (pinfunction "K_1") (pintype "input"))
      (node (ref "D290") (pin "1") (pinfunction "K_1") (pintype "input"))
      (node (ref "R222") (pin "2") (pinfunction "2_2") (pintype "input"))
    )
    (net (code "142") (name "ROW5_R") (class "Default")
      (node (ref "R222") (pin "1") (pinfunction "1_1") (pintype "input"))
      (node (ref "U101") (pin "29") (pinfunction "GPIO18_29") (pintype "bidirectional"))
    )
    (net (code "143") (name "RS") (class "Default")
      (node (ref "FPC1") (pin "3") (pinfunction "3_3") (pintype "unspecified"))
      (node (ref "U101") (pin "34") (pinfunction "GPIO22_34") (pintype "bidirectional"))
    )
    (net (code "144") (name "RSTB") (class "Default")
      (node (ref "FPC1") (pin "4") (pinfunction "4_4") (pintype "unspecified"))
      (node (ref "U101") (pin "40") (pinfunction "GPIO28_ADC2_40") (pintype "bidirectional"))
    )
    (net (code "145") (name "SCL") (class "Default")
      (node (ref "FPC1") (pin "2") (pinfunction "2_2") (pintype "unspecified"))
      (node (ref "U101") (pin "39") (pinfunction "GPIO27_ADC1_39") (pintype "bidirectional"))
    )
    (net (code "146") (name "SDA") (class "Default")
      (node (ref "FPC1") (pin "1") (pinfunction "1_1") (pintype "unspecified"))
      (node (ref "U101") (pin "38") (pinfunction "GPIO26_ADC0_38") (pintype "bidirectional"))
    )
    (net (code "147") (name "SWCLK") (class "Default")
      (node (ref "J102") (pin "1") (pinfunction "1_1") (pintype "input"))
      (node (ref "U101") (pin "24") (pinfunction "SWCLK_24") (pintype "output"))
    )
    (net (code "148") (name "SWDIO") (class "Default")
      (node (ref "J102") (pin "3") (pinfunction "3_3") (pintype "input"))
      (node (ref "U101") (pin "25") (pinfunction "SWD_25") (pintype "bidirectional"))
    )
    (net (code "149") (name "TE") (class "Default")
      (node (ref "FPC1") (pin "6") (pinfunction "6_6") (pintype "unspecified"))
      (node (ref "U101") (pin "41") (pinfunction "GPIO29_ADC3_41") (pintype "bidirectional"))
    )
    (net (code "150") (name "USB_N") (class "Default")
      (node (ref "R109") (pin "2") (pinfunction "2_2") (pintype "input"))
      (node (ref "U101") (pin "46") (pinfunction "USB_DM_46") (pintype "bidirectional"))
    )
    (net (code "151") (name "USB_P") (class "Default")
      (node (ref "R111") (pin "2") (pinfunction "2_2") (pintype "input"))
      (node (ref "U101") (pin "47") (pinfunction "USB_DP_47") (pintype "bidirectional"))
    )
    (net (code "152") (name "XIN") (class "Default")
      (node (ref "C123") (pin "1") (pinfunction "1_1") (pintype "unspecified"))
      (node (ref "R120") (pin "2") (pinfunction "2_2") (pintype "input"))
      (node (ref "U101") (pin "20") (pinfunction "XIN_20") (pintype "input"))
      (node (ref "Y101") (pin "1") (pinfunction "1_1") (pintype "input"))
    )
    (net (code "153") (name "XOUT") (class "Default")
      (node (ref "R120") (pin "1") (pinfunction "1_1") (pintype "input"))
      (node (ref "R121") (pin "2") (pinfunction "2_2") (pintype "input"))
      (node (ref "U101") (pin "21") (pinfunction "XOUT_21") (pintype "unspecified"))
    )
    (net (code "154") (name "X_R") (class "Default")
      (node (ref "C124") (pin "1") (pinfunction "1_1") (pintype "unspecified"))
      (node (ref "R121") (pin "1") (pinfunction "1_1") (pintype "input"))
      (node (ref "Y101") (pin "3") (pinfunction "3_3") (pintype "input"))
    )
    (net (code "155") (name "unconnected-(ENC201-Pad1)") (class "Default")
      (node (ref "ENC201") (pin "1") (pinfunction "1_1") (pintype "input+no_connect"))
    )
    (net (code "156") (name "unconnected-(ENC201-Pad2)") (class "Default")
      (node (ref "ENC201") (pin "2") (pinfunction "2_2") (pintype "input+no_connect"))
    )
    (net (code "157") (name "unconnected-(FPC1-Pad11)") (class "Default")
      (node (ref "FPC1") (pin "11") (pinfunction "11_11") (pintype "unspecified+no_connect"))
    )
    (net (code "158") (name "unconnected-(FPC1-Pad12)") (class "Default")
      (node (ref "FPC1") (pin "12") (pinfunction "12_12") (pintype "unspecified+no_connect"))
    )
    (net (code "159") (name "unconnected-(J101-SBU1-Pad9)") (class "Default")
      (node (ref "J101") (pin "9") (pinfunction "SBU1_9") (pintype "unspecified+no_connect"))
    )
    (net (code "160") (name "unconnected-(J101-SBU2-Pad3)") (class "Default")
      (node (ref "J101") (pin "3") (pinfunction "SBU2_3") (pintype "unspecified+no_connect"))
    )
    (net (code "161") (name "unconnected-(U101-GPIO23-Pad35)") (class "Default")
      (node (ref "U101") (pin "35") (pinfunction "GPIO23_35") (pintype "bidirectional+no_connect"))
    )
    (net (code "162") (name "unconnected-(U101-GPIO24-Pad36)") (class "Default")
      (node (ref "U101") (pin "36") (pinfunction "GPIO24_36") (pintype "bidirectional+no_connect"))
    )
    (net (code "163") (name "unconnected-(U101-GPIO25-Pad37)") (class "Default")
      (node (ref "U101") (pin "37") (pinfunction "GPIO25_37") (pintype "bidirectional+no_connect"))
    )
  )
)
